# Module_Relay_UART_CAN.net
KiCad netlist of a schematic drawn in Altium Designer
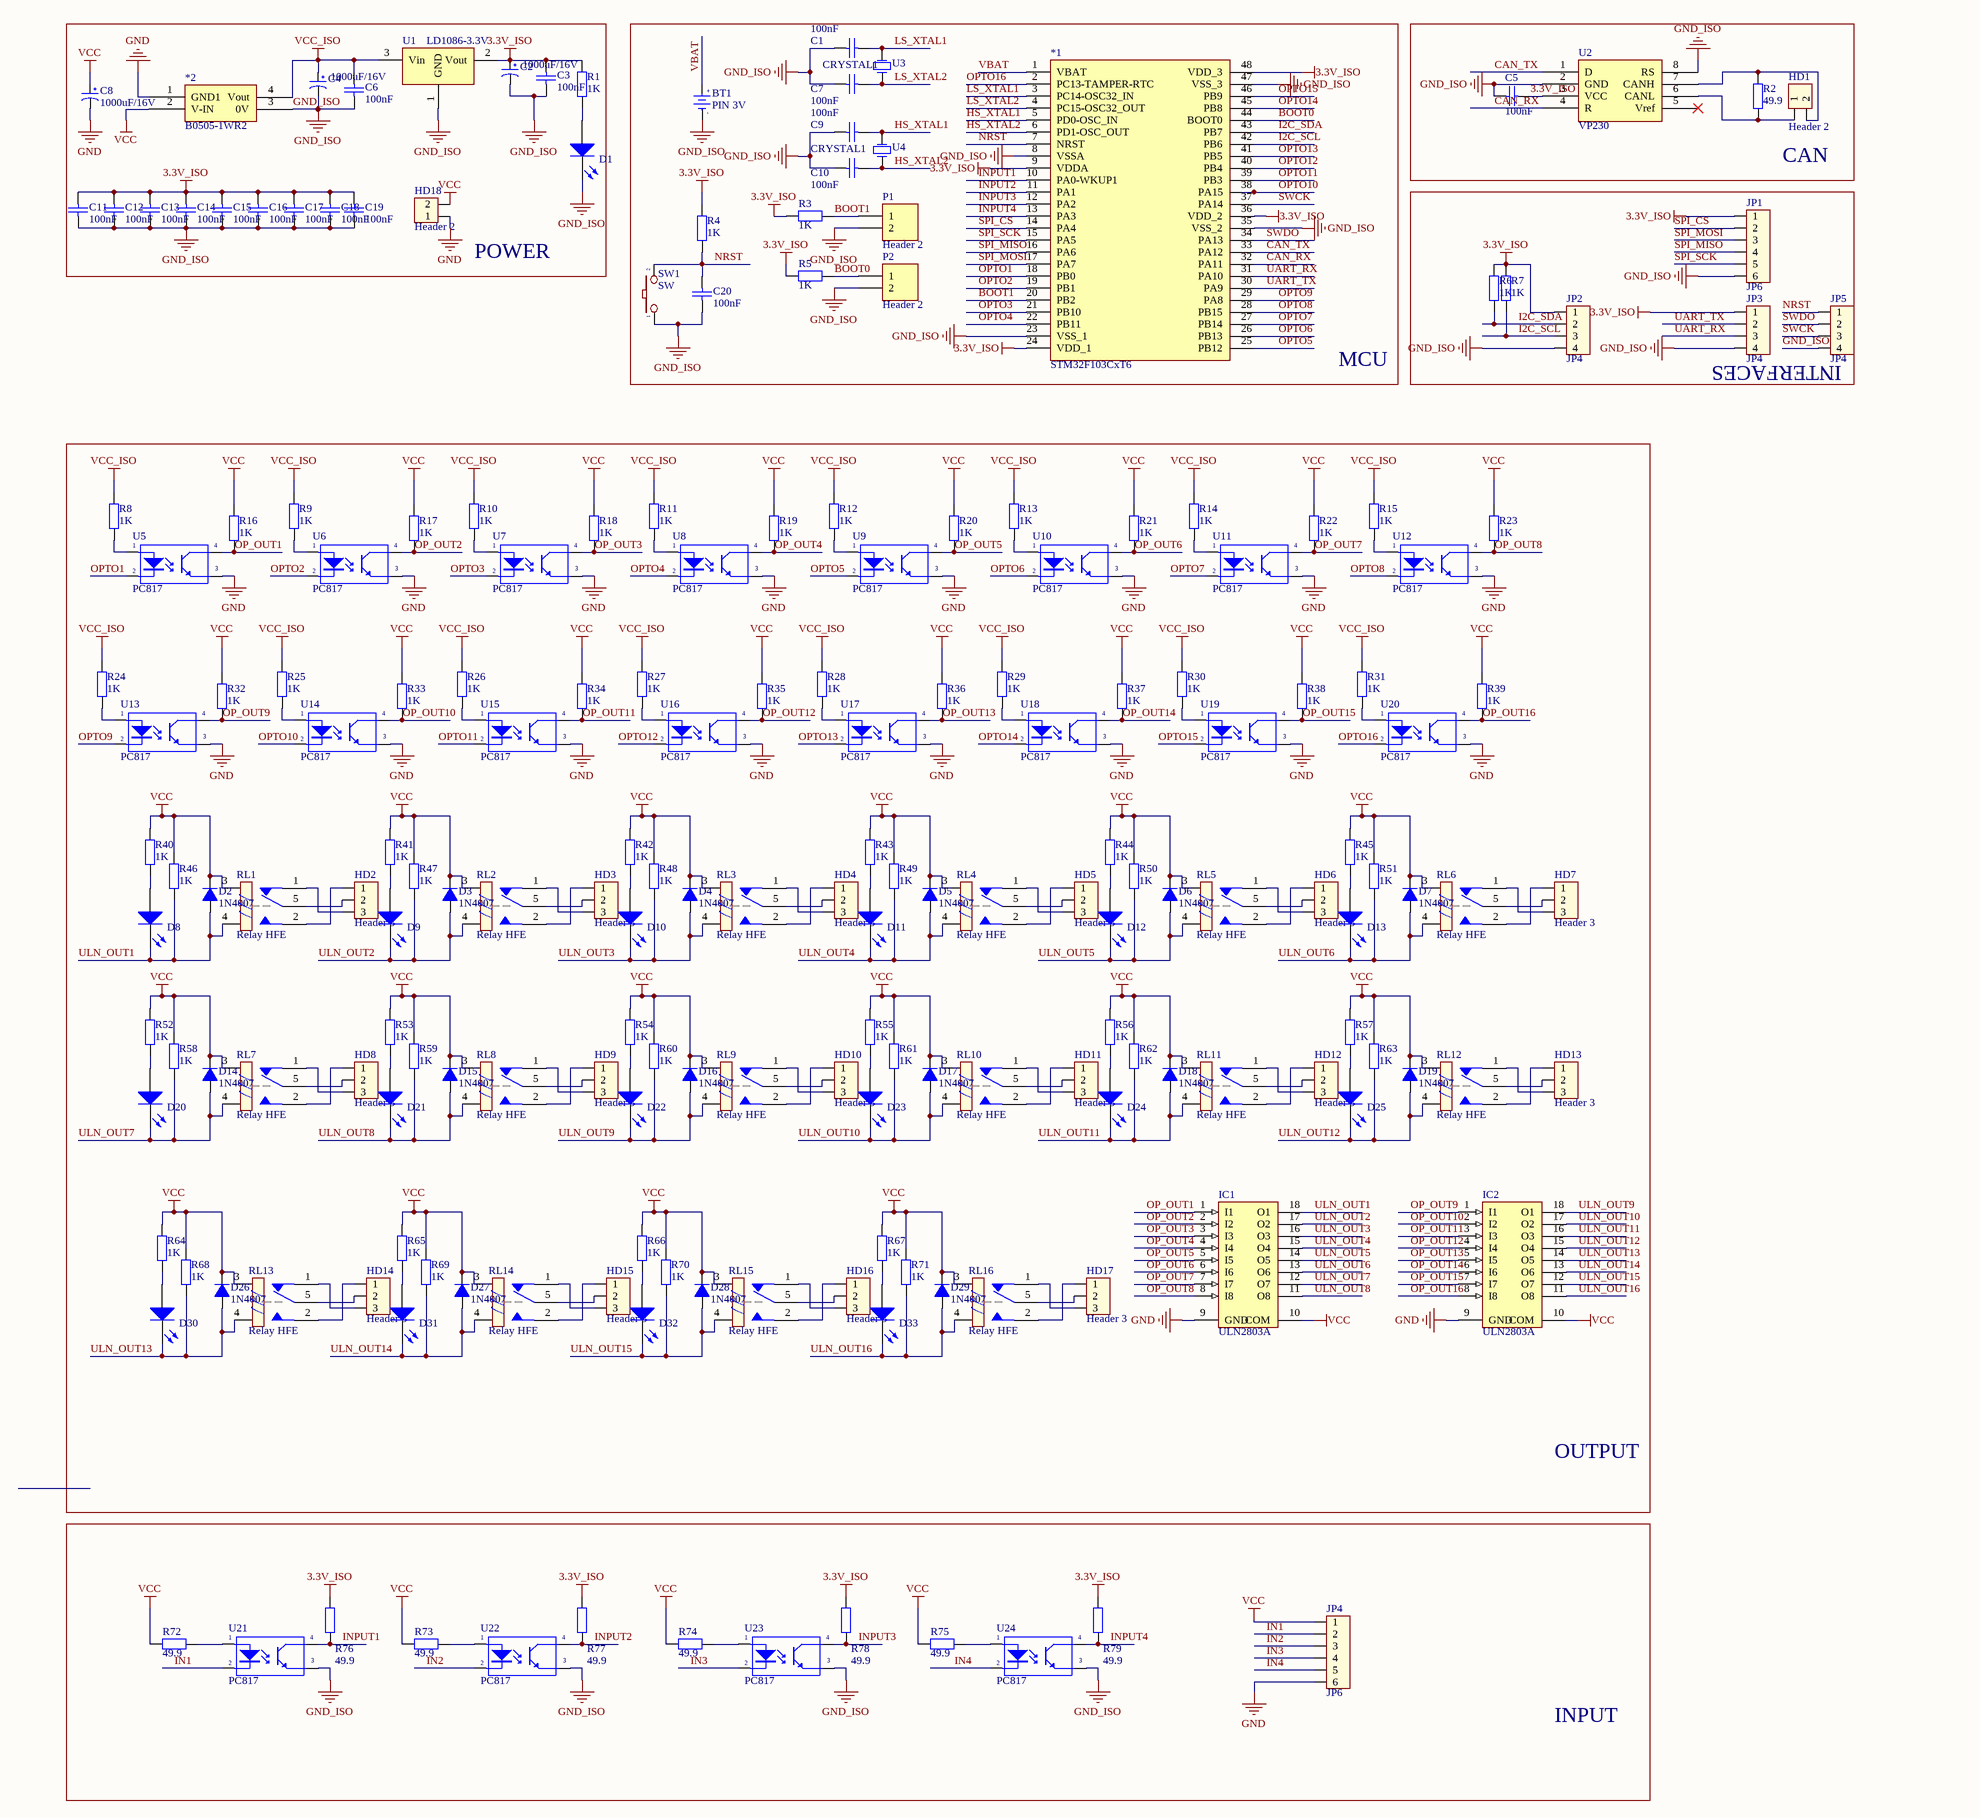
[diagram p0: Module_Relay_UART_CAN.SchDoc]

(export (version "E")
  (design (tool "Eeschema 10.0.6"))
  (components
    (comp (ref "*1")
      (value "STM32F103CxT6")
      (footprint "LQFP48_N")
      (libsource (lib "HTSAIGON") (part "STM32F103CxT6"))
    )
    (comp (ref "*2")
      (value "B0505-1WR2")
      (footprint "B0505-1WR2")
      (libsource (lib "HTSAIGON") (part "B0505-1WR2"))
    )
    (comp (ref "BT1")
      (value "PIN 3V")
      (footprint "CR1220")
      (description "Battery 3VDC")
      (libsource (lib "HTSAIGON") (part "PIN 3V"))
    )
    (comp (ref "C1")
      (value "CAP")
      (footprint "CAP0805")
      (fields (field (name "CAP") "100nF"))
      (libsource (lib "HTSAIGON") (part "CAP"))
    )
    (comp (ref "C2")
      (value "1000uF/16V")
      (footprint "CAP2917")
      (description "Cap 1000uF/16V - 220uF/50V")
      (libsource (lib "HTSAIGON") (part "CP4"))
    )
    (comp (ref "C3")
      (value "CAP")
      (footprint "CAP0805")
      (fields (field (name "CAP") "100nF"))
      (libsource (lib "HTSAIGON") (part "CAP"))
    )
    (comp (ref "C4")
      (value "1000uF/16V")
      (footprint "CAP2917")
      (description "Cap 1000uF/16V - 220uF/50V")
      (libsource (lib "HTSAIGON") (part "CP4"))
    )
    (comp (ref "C5")
      (value "CAP")
      (footprint "CAP0805")
      (fields (field (name "CAP") "100nF"))
      (libsource (lib "HTSAIGON") (part "CAP"))
    )
    (comp (ref "C6")
      (value "CAP")
      (footprint "CAP0805")
      (fields (field (name "CAP") "100nF"))
      (libsource (lib "HTSAIGON") (part "CAP"))
    )
    (comp (ref "C7")
      (value "CAP")
      (footprint "CAP0805")
      (fields (field (name "CAP") "100nF"))
      (libsource (lib "HTSAIGON") (part "CAP"))
    )
    (comp (ref "C8")
      (value "1000uF/16V")
      (footprint "CAP2917")
      (description "Cap 1000uF/16V - 220uF/50V")
      (libsource (lib "HTSAIGON") (part "CP4"))
    )
    (comp (ref "C9")
      (value "CAP")
      (footprint "CAP0805")
      (fields (field (name "CAP") "100nF"))
      (libsource (lib "HTSAIGON") (part "CAP"))
    )
    (comp (ref "C10")
      (value "CAP")
      (footprint "CAP0805")
      (fields (field (name "CAP") "100nF"))
      (libsource (lib "HTSAIGON") (part "CAP"))
    )
    (comp (ref "C11")
      (value "CAP")
      (footprint "CAP0805")
      (fields (field (name "CAP") "100nF"))
      (libsource (lib "HTSAIGON") (part "CAP"))
    )
    (comp (ref "C12")
      (value "CAP")
      (footprint "CAP0805")
      (fields (field (name "CAP") "100nF"))
      (libsource (lib "HTSAIGON") (part "CAP"))
    )
    (comp (ref "C13")
      (value "CAP")
      (footprint "CAP0805")
      (fields (field (name "CAP") "100nF"))
      (libsource (lib "HTSAIGON") (part "CAP"))
    )
    (comp (ref "C14")
      (value "CAP")
      (footprint "CAP0805")
      (fields (field (name "CAP") "100nF"))
      (libsource (lib "HTSAIGON") (part "CAP"))
    )
    (comp (ref "C15")
      (value "CAP")
      (footprint "CAP0805")
      (fields (field (name "CAP") "100nF"))
      (libsource (lib "HTSAIGON") (part "CAP"))
    )
    (comp (ref "C16")
      (value "CAP")
      (footprint "CAP0805")
      (fields (field (name "CAP") "100nF"))
      (libsource (lib "HTSAIGON") (part "CAP"))
    )
    (comp (ref "C17")
      (value "CAP")
      (footprint "CAP0805")
      (fields (field (name "CAP") "100nF"))
      (libsource (lib "HTSAIGON") (part "CAP"))
    )
    (comp (ref "C18")
      (value "CAP")
      (footprint "CAP0805")
      (fields (field (name "CAP") "100nF"))
      (libsource (lib "HTSAIGON") (part "CAP"))
    )
    (comp (ref "C19")
      (value "CAP")
      (footprint "CAP0805")
      (fields (field (name "CAP") "100nF"))
      (libsource (lib "HTSAIGON") (part "CAP"))
    )
    (comp (ref "C20")
      (value "CAP")
      (footprint "CAP0805")
      (fields (field (name "CAP") "100nF"))
      (libsource (lib "HTSAIGON") (part "CAP"))
    )
    (comp (ref "D1") (value "LED") (footprint "LED0805") (libsource (lib "HTSAIGON") (part "LED1")))
    (comp (ref "D2")
      (value "1N4007")
      (footprint "D1A")
      (description "Diode 1A")
      (libsource (lib "HTSAIGON") (part "D1A"))
    )
    (comp (ref "D3")
      (value "1N4007")
      (footprint "D1A")
      (description "Diode 1A")
      (libsource (lib "HTSAIGON") (part "D1A"))
    )
    (comp (ref "D4")
      (value "1N4007")
      (footprint "D1A")
      (description "Diode 1A")
      (libsource (lib "HTSAIGON") (part "D1A"))
    )
    (comp (ref "D5")
      (value "1N4007")
      (footprint "D1A")
      (description "Diode 1A")
      (libsource (lib "HTSAIGON") (part "D1A"))
    )
    (comp (ref "D6")
      (value "1N4007")
      (footprint "D1A")
      (description "Diode 1A")
      (libsource (lib "HTSAIGON") (part "D1A"))
    )
    (comp (ref "D7")
      (value "1N4007")
      (footprint "D1A")
      (description "Diode 1A")
      (libsource (lib "HTSAIGON") (part "D1A"))
    )
    (comp (ref "D8") (value "LED") (footprint "LED0805") (libsource (lib "HTSAIGON") (part "LED1")))
    (comp (ref "D9") (value "LED") (footprint "LED0805") (libsource (lib "HTSAIGON") (part "LED1")))
    (comp (ref "D10") (value "LED") (footprint "LED0805") (libsource (lib "HTSAIGON") (part "LED1")))
    (comp (ref "D11") (value "LED") (footprint "LED0805") (libsource (lib "HTSAIGON") (part "LED1")))
    (comp (ref "D12") (value "LED") (footprint "LED0805") (libsource (lib "HTSAIGON") (part "LED1")))
    (comp (ref "D13") (value "LED") (footprint "LED0805") (libsource (lib "HTSAIGON") (part "LED1")))
    (comp (ref "D14")
      (value "1N4007")
      (footprint "D1A")
      (description "Diode 1A")
      (libsource (lib "HTSAIGON") (part "D1A"))
    )
    (comp (ref "D15")
      (value "1N4007")
      (footprint "D1A")
      (description "Diode 1A")
      (libsource (lib "HTSAIGON") (part "D1A"))
    )
    (comp (ref "D16")
      (value "1N4007")
      (footprint "D1A")
      (description "Diode 1A")
      (libsource (lib "HTSAIGON") (part "D1A"))
    )
    (comp (ref "D17")
      (value "1N4007")
      (footprint "D1A")
      (description "Diode 1A")
      (libsource (lib "HTSAIGON") (part "D1A"))
    )
    (comp (ref "D18")
      (value "1N4007")
      (footprint "D1A")
      (description "Diode 1A")
      (libsource (lib "HTSAIGON") (part "D1A"))
    )
    (comp (ref "D19")
      (value "1N4007")
      (footprint "D1A")
      (description "Diode 1A")
      (libsource (lib "HTSAIGON") (part "D1A"))
    )
    (comp (ref "D20") (value "LED") (footprint "LED0805") (libsource (lib "HTSAIGON") (part "LED1")))
    (comp (ref "D21") (value "LED") (footprint "LED0805") (libsource (lib "HTSAIGON") (part "LED1")))
    (comp (ref "D22") (value "LED") (footprint "LED0805") (libsource (lib "HTSAIGON") (part "LED1")))
    (comp (ref "D23") (value "LED") (footprint "LED0805") (libsource (lib "HTSAIGON") (part "LED1")))
    (comp (ref "D24") (value "LED") (footprint "LED0805") (libsource (lib "HTSAIGON") (part "LED1")))
    (comp (ref "D25") (value "LED") (footprint "LED0805") (libsource (lib "HTSAIGON") (part "LED1")))
    (comp (ref "D26")
      (value "1N4007")
      (footprint "D1A")
      (description "Diode 1A")
      (libsource (lib "HTSAIGON") (part "D1A"))
    )
    (comp (ref "D27")
      (value "1N4007")
      (footprint "D1A")
      (description "Diode 1A")
      (libsource (lib "HTSAIGON") (part "D1A"))
    )
    (comp (ref "D28")
      (value "1N4007")
      (footprint "D1A")
      (description "Diode 1A")
      (libsource (lib "HTSAIGON") (part "D1A"))
    )
    (comp (ref "D29")
      (value "1N4007")
      (footprint "D1A")
      (description "Diode 1A")
      (libsource (lib "HTSAIGON") (part "D1A"))
    )
    (comp (ref "D30") (value "LED") (footprint "LED0805") (libsource (lib "HTSAIGON") (part "LED1")))
    (comp (ref "D31") (value "LED") (footprint "LED0805") (libsource (lib "HTSAIGON") (part "LED1")))
    (comp (ref "D32") (value "LED") (footprint "LED0805") (libsource (lib "HTSAIGON") (part "LED1")))
    (comp (ref "D33") (value "LED") (footprint "LED0805") (libsource (lib "HTSAIGON") (part "LED1")))
    (comp (ref "HD1")
      (value "Header 2")
      (footprint "HED2T")
      (description "Header 2 (Green)")
      (libsource (lib "") (part "Hed2_1"))
    )
    (comp (ref "HD2")
      (value "Header 3")
      (footprint "HED3T")
      (description "Header 3 (Green)")
      (libsource (lib "HTSAIGON") (part "Hed3"))
    )
    (comp (ref "HD3")
      (value "Header 3")
      (footprint "HED3T")
      (description "Header 3 (Green)")
      (libsource (lib "HTSAIGON") (part "Hed3"))
    )
    (comp (ref "HD4")
      (value "Header 3")
      (footprint "HED3T")
      (description "Header 3 (Green)")
      (libsource (lib "HTSAIGON") (part "Hed3"))
    )
    (comp (ref "HD5")
      (value "Header 3")
      (footprint "HED3T")
      (description "Header 3 (Green)")
      (libsource (lib "HTSAIGON") (part "Hed3"))
    )
    (comp (ref "HD6")
      (value "Header 3")
      (footprint "HED3T")
      (description "Header 3 (Green)")
      (libsource (lib "HTSAIGON") (part "Hed3"))
    )
    (comp (ref "HD7")
      (value "Header 3")
      (footprint "HED3T")
      (description "Header 3 (Green)")
      (libsource (lib "HTSAIGON") (part "Hed3"))
    )
    (comp (ref "HD8")
      (value "Header 3")
      (footprint "HED3T")
      (description "Header 3 (Green)")
      (libsource (lib "HTSAIGON") (part "Hed3"))
    )
    (comp (ref "HD9")
      (value "Header 3")
      (footprint "HED3T")
      (description "Header 3 (Green)")
      (libsource (lib "HTSAIGON") (part "Hed3"))
    )
    (comp (ref "HD10")
      (value "Header 3")
      (footprint "HED3T")
      (description "Header 3 (Green)")
      (libsource (lib "HTSAIGON") (part "Hed3"))
    )
    (comp (ref "HD11")
      (value "Header 3")
      (footprint "HED3T")
      (description "Header 3 (Green)")
      (libsource (lib "HTSAIGON") (part "Hed3"))
    )
    (comp (ref "HD12")
      (value "Header 3")
      (footprint "HED3T")
      (description "Header 3 (Green)")
      (libsource (lib "HTSAIGON") (part "Hed3"))
    )
    (comp (ref "HD13")
      (value "Header 3")
      (footprint "HED3T")
      (description "Header 3 (Green)")
      (libsource (lib "HTSAIGON") (part "Hed3"))
    )
    (comp (ref "HD14")
      (value "Header 3")
      (footprint "HED3T")
      (description "Header 3 (Green)")
      (libsource (lib "HTSAIGON") (part "Hed3"))
    )
    (comp (ref "HD15")
      (value "Header 3")
      (footprint "HED3T")
      (description "Header 3 (Green)")
      (libsource (lib "HTSAIGON") (part "Hed3"))
    )
    (comp (ref "HD16")
      (value "Header 3")
      (footprint "HED3T")
      (description "Header 3 (Green)")
      (libsource (lib "HTSAIGON") (part "Hed3"))
    )
    (comp (ref "HD17")
      (value "Header 3")
      (footprint "HED3T")
      (description "Header 3 (Green)")
      (libsource (lib "HTSAIGON") (part "Hed3"))
    )
    (comp (ref "HD18")
      (value "Header 2")
      (footprint "HED2T")
      (description "Header 2 (Green)")
      (libsource (lib "HTSAIGON") (part "Hed2"))
    )
    (comp (ref "IC1")
      (value "ULN2803A")
      (footprint "SOP18")
      (description "High-Voltage, High-Current Darlington Array")
      (fields (field (name "PUBLISHER") "Altium Limited"))
      (libsource (lib "HTSAIGON") (part "ULN2803A"))
    )
    (comp (ref "IC2")
      (value "ULN2803A")
      (footprint "SOP18")
      (description "High-Voltage, High-Current Darlington Array")
      (fields (field (name "PUBLISHER") "Altium Limited"))
      (libsource (lib "HTSAIGON") (part "ULN2803A"))
    )
    (comp (ref "JP1")
      (value "JP6")
      (footprint "CON6")
      (description "Connector 6")
      (libsource (lib "HTSAIGON") (part "Con6"))
    )
    (comp (ref "JP2")
      (value "JP4")
      (footprint "CON4")
      (description "Connector 4")
      (libsource (lib "HTSAIGON") (part "Con4"))
    )
    (comp (ref "JP3")
      (value "JP4")
      (footprint "CON4")
      (description "Connector 4")
      (libsource (lib "HTSAIGON") (part "Con4"))
    )
    (comp (ref "JP4")
      (value "JP6")
      (footprint "CON6")
      (description "Connector 6")
      (libsource (lib "HTSAIGON") (part "Con6"))
    )
    (comp (ref "JP5")
      (value "JP4")
      (footprint "CON4")
      (description "Connector 4")
      (libsource (lib "HTSAIGON") (part "Con4"))
    )
    (comp (ref "P1")
      (value "Header 2")
      (footprint "HDR1X2")
      (description "Header, 2-Pin")
      (fields (field (name "PUBLISHER") "Altium Limited"))
      (libsource (lib "Miscellaneous Connectors") (part "Header 2"))
    )
    (comp (ref "P2")
      (value "Header 2")
      (footprint "HDR1X2")
      (description "Header, 2-Pin")
      (fields (field (name "PUBLISHER") "Altium Limited"))
      (libsource (lib "Miscellaneous Connectors") (part "Header 2"))
    )
    (comp (ref "R1")
      (value "RES")
      (footprint "0805")
      (fields (field (name "RES") "1K"))
      (libsource (lib "HTSAIGON") (part "RES"))
    )
    (comp (ref "R2")
      (value "RES")
      (footprint "0805")
      (fields (field (name "RES") "49.9"))
      (libsource (lib "") (part "RES_1"))
    )
    (comp (ref "R3")
      (value "RES")
      (footprint "0805")
      (fields (field (name "RES") "1K"))
      (libsource (lib "") (part "RES_3"))
    )
    (comp (ref "R4")
      (value "RES")
      (footprint "0805")
      (fields (field (name "RES") "1K"))
      (libsource (lib "HTSAIGON") (part "RES"))
    )
    (comp (ref "R5")
      (value "RES")
      (footprint "0805")
      (fields (field (name "RES") "1K"))
      (libsource (lib "") (part "RES_3"))
    )
    (comp (ref "R6")
      (value "RES")
      (footprint "0805")
      (fields (field (name "RES") "1K"))
      (libsource (lib "HTSAIGON") (part "RES"))
    )
    (comp (ref "R7")
      (value "RES")
      (footprint "0805")
      (fields (field (name "RES") "1K"))
      (libsource (lib "HTSAIGON") (part "RES"))
    )
    (comp (ref "R8")
      (value "RES")
      (footprint "0805")
      (fields (field (name "RES") "1K"))
      (libsource (lib "") (part "RES_1"))
    )
    (comp (ref "R9")
      (value "RES")
      (footprint "0805")
      (fields (field (name "RES") "1K"))
      (libsource (lib "") (part "RES_1"))
    )
    (comp (ref "R10")
      (value "RES")
      (footprint "0805")
      (fields (field (name "RES") "1K"))
      (libsource (lib "") (part "RES_1"))
    )
    (comp (ref "R11")
      (value "RES")
      (footprint "0805")
      (fields (field (name "RES") "1K"))
      (libsource (lib "") (part "RES_1"))
    )
    (comp (ref "R12")
      (value "RES")
      (footprint "0805")
      (fields (field (name "RES") "1K"))
      (libsource (lib "") (part "RES_1"))
    )
    (comp (ref "R13")
      (value "RES")
      (footprint "0805")
      (fields (field (name "RES") "1K"))
      (libsource (lib "") (part "RES_1"))
    )
    (comp (ref "R14")
      (value "RES")
      (footprint "0805")
      (fields (field (name "RES") "1K"))
      (libsource (lib "") (part "RES_1"))
    )
    (comp (ref "R15")
      (value "RES")
      (footprint "0805")
      (fields (field (name "RES") "1K"))
      (libsource (lib "") (part "RES_1"))
    )
    (comp (ref "R16")
      (value "RES")
      (footprint "0805")
      (fields (field (name "RES") "1K"))
      (libsource (lib "HTSAIGON") (part "RES"))
    )
    (comp (ref "R17")
      (value "RES")
      (footprint "0805")
      (fields (field (name "RES") "1K"))
      (libsource (lib "HTSAIGON") (part "RES"))
    )
    (comp (ref "R18")
      (value "RES")
      (footprint "0805")
      (fields (field (name "RES") "1K"))
      (libsource (lib "HTSAIGON") (part "RES"))
    )
    (comp (ref "R19")
      (value "RES")
      (footprint "0805")
      (fields (field (name "RES") "1K"))
      (libsource (lib "HTSAIGON") (part "RES"))
    )
    (comp (ref "R20")
      (value "RES")
      (footprint "0805")
      (fields (field (name "RES") "1K"))
      (libsource (lib "HTSAIGON") (part "RES"))
    )
    (comp (ref "R21")
      (value "RES")
      (footprint "0805")
      (fields (field (name "RES") "1K"))
      (libsource (lib "HTSAIGON") (part "RES"))
    )
    (comp (ref "R22")
      (value "RES")
      (footprint "0805")
      (fields (field (name "RES") "1K"))
      (libsource (lib "HTSAIGON") (part "RES"))
    )
    (comp (ref "R23")
      (value "RES")
      (footprint "0805")
      (fields (field (name "RES") "1K"))
      (libsource (lib "HTSAIGON") (part "RES"))
    )
    (comp (ref "R24")
      (value "RES")
      (footprint "0805")
      (fields (field (name "RES") "1K"))
      (libsource (lib "") (part "RES_1"))
    )
    (comp (ref "R25")
      (value "RES")
      (footprint "0805")
      (fields (field (name "RES") "1K"))
      (libsource (lib "") (part "RES_1"))
    )
    (comp (ref "R26")
      (value "RES")
      (footprint "0805")
      (fields (field (name "RES") "1K"))
      (libsource (lib "") (part "RES_1"))
    )
    (comp (ref "R27")
      (value "RES")
      (footprint "0805")
      (fields (field (name "RES") "1K"))
      (libsource (lib "") (part "RES_1"))
    )
    (comp (ref "R28")
      (value "RES")
      (footprint "0805")
      (fields (field (name "RES") "1K"))
      (libsource (lib "") (part "RES_1"))
    )
    (comp (ref "R29")
      (value "RES")
      (footprint "0805")
      (fields (field (name "RES") "1K"))
      (libsource (lib "") (part "RES_1"))
    )
    (comp (ref "R30")
      (value "RES")
      (footprint "0805")
      (fields (field (name "RES") "1K"))
      (libsource (lib "") (part "RES_1"))
    )
    (comp (ref "R31")
      (value "RES")
      (footprint "0805")
      (fields (field (name "RES") "1K"))
      (libsource (lib "") (part "RES_1"))
    )
    (comp (ref "R32")
      (value "RES")
      (footprint "0805")
      (fields (field (name "RES") "1K"))
      (libsource (lib "HTSAIGON") (part "RES"))
    )
    (comp (ref "R33")
      (value "RES")
      (footprint "0805")
      (fields (field (name "RES") "1K"))
      (libsource (lib "HTSAIGON") (part "RES"))
    )
    (comp (ref "R34")
      (value "RES")
      (footprint "0805")
      (fields (field (name "RES") "1K"))
      (libsource (lib "HTSAIGON") (part "RES"))
    )
    (comp (ref "R35")
      (value "RES")
      (footprint "0805")
      (fields (field (name "RES") "1K"))
      (libsource (lib "HTSAIGON") (part "RES"))
    )
    (comp (ref "R36")
      (value "RES")
      (footprint "0805")
      (fields (field (name "RES") "1K"))
      (libsource (lib "HTSAIGON") (part "RES"))
    )
    (comp (ref "R37")
      (value "RES")
      (footprint "0805")
      (fields (field (name "RES") "1K"))
      (libsource (lib "HTSAIGON") (part "RES"))
    )
    (comp (ref "R38")
      (value "RES")
      (footprint "0805")
      (fields (field (name "RES") "1K"))
      (libsource (lib "HTSAIGON") (part "RES"))
    )
    (comp (ref "R39")
      (value "RES")
      (footprint "0805")
      (fields (field (name "RES") "1K"))
      (libsource (lib "HTSAIGON") (part "RES"))
    )
    (comp (ref "R40")
      (value "RES")
      (footprint "0805")
      (fields (field (name "RES") "1K"))
      (libsource (lib "HTSAIGON") (part "RES"))
    )
    (comp (ref "R41")
      (value "RES")
      (footprint "0805")
      (fields (field (name "RES") "1K"))
      (libsource (lib "HTSAIGON") (part "RES"))
    )
    (comp (ref "R42")
      (value "RES")
      (footprint "0805")
      (fields (field (name "RES") "1K"))
      (libsource (lib "HTSAIGON") (part "RES"))
    )
    (comp (ref "R43")
      (value "RES")
      (footprint "0805")
      (fields (field (name "RES") "1K"))
      (libsource (lib "HTSAIGON") (part "RES"))
    )
    (comp (ref "R44")
      (value "RES")
      (footprint "0805")
      (fields (field (name "RES") "1K"))
      (libsource (lib "HTSAIGON") (part "RES"))
    )
    (comp (ref "R45")
      (value "RES")
      (footprint "0805")
      (fields (field (name "RES") "1K"))
      (libsource (lib "HTSAIGON") (part "RES"))
    )
    (comp (ref "R46")
      (value "RES")
      (footprint "0805")
      (fields (field (name "RES") "1K"))
      (libsource (lib "HTSAIGON") (part "RES"))
    )
    (comp (ref "R47")
      (value "RES")
      (footprint "0805")
      (fields (field (name "RES") "1K"))
      (libsource (lib "HTSAIGON") (part "RES"))
    )
    (comp (ref "R48")
      (value "RES")
      (footprint "0805")
      (fields (field (name "RES") "1K"))
      (libsource (lib "HTSAIGON") (part "RES"))
    )
    (comp (ref "R49")
      (value "RES")
      (footprint "0805")
      (fields (field (name "RES") "1K"))
      (libsource (lib "HTSAIGON") (part "RES"))
    )
    (comp (ref "R50")
      (value "RES")
      (footprint "0805")
      (fields (field (name "RES") "1K"))
      (libsource (lib "HTSAIGON") (part "RES"))
    )
    (comp (ref "R51")
      (value "RES")
      (footprint "0805")
      (fields (field (name "RES") "1K"))
      (libsource (lib "HTSAIGON") (part "RES"))
    )
    (comp (ref "R52")
      (value "RES")
      (footprint "0805")
      (fields (field (name "RES") "1K"))
      (libsource (lib "HTSAIGON") (part "RES"))
    )
    (comp (ref "R53")
      (value "RES")
      (footprint "0805")
      (fields (field (name "RES") "1K"))
      (libsource (lib "HTSAIGON") (part "RES"))
    )
    (comp (ref "R54")
      (value "RES")
      (footprint "0805")
      (fields (field (name "RES") "1K"))
      (libsource (lib "HTSAIGON") (part "RES"))
    )
    (comp (ref "R55")
      (value "RES")
      (footprint "0805")
      (fields (field (name "RES") "1K"))
      (libsource (lib "HTSAIGON") (part "RES"))
    )
    (comp (ref "R56")
      (value "RES")
      (footprint "0805")
      (fields (field (name "RES") "1K"))
      (libsource (lib "HTSAIGON") (part "RES"))
    )
    (comp (ref "R57")
      (value "RES")
      (footprint "0805")
      (fields (field (name "RES") "1K"))
      (libsource (lib "HTSAIGON") (part "RES"))
    )
    (comp (ref "R58")
      (value "RES")
      (footprint "0805")
      (fields (field (name "RES") "1K"))
      (libsource (lib "HTSAIGON") (part "RES"))
    )
    (comp (ref "R59")
      (value "RES")
      (footprint "0805")
      (fields (field (name "RES") "1K"))
      (libsource (lib "HTSAIGON") (part "RES"))
    )
    (comp (ref "R60")
      (value "RES")
      (footprint "0805")
      (fields (field (name "RES") "1K"))
      (libsource (lib "HTSAIGON") (part "RES"))
    )
    (comp (ref "R61")
      (value "RES")
      (footprint "0805")
      (fields (field (name "RES") "1K"))
      (libsource (lib "HTSAIGON") (part "RES"))
    )
    (comp (ref "R62")
      (value "RES")
      (footprint "0805")
      (fields (field (name "RES") "1K"))
      (libsource (lib "HTSAIGON") (part "RES"))
    )
    (comp (ref "R63")
      (value "RES")
      (footprint "0805")
      (fields (field (name "RES") "1K"))
      (libsource (lib "HTSAIGON") (part "RES"))
    )
    (comp (ref "R64")
      (value "RES")
      (footprint "0805")
      (fields (field (name "RES") "1K"))
      (libsource (lib "HTSAIGON") (part "RES"))
    )
    (comp (ref "R65")
      (value "RES")
      (footprint "0805")
      (fields (field (name "RES") "1K"))
      (libsource (lib "HTSAIGON") (part "RES"))
    )
    (comp (ref "R66")
      (value "RES")
      (footprint "0805")
      (fields (field (name "RES") "1K"))
      (libsource (lib "HTSAIGON") (part "RES"))
    )
    (comp (ref "R67")
      (value "RES")
      (footprint "0805")
      (fields (field (name "RES") "1K"))
      (libsource (lib "HTSAIGON") (part "RES"))
    )
    (comp (ref "R68")
      (value "RES")
      (footprint "0805")
      (fields (field (name "RES") "1K"))
      (libsource (lib "HTSAIGON") (part "RES"))
    )
    (comp (ref "R69")
      (value "RES")
      (footprint "0805")
      (fields (field (name "RES") "1K"))
      (libsource (lib "HTSAIGON") (part "RES"))
    )
    (comp (ref "R70")
      (value "RES")
      (footprint "0805")
      (fields (field (name "RES") "1K"))
      (libsource (lib "HTSAIGON") (part "RES"))
    )
    (comp (ref "R71")
      (value "RES")
      (footprint "0805")
      (fields (field (name "RES") "1K"))
      (libsource (lib "HTSAIGON") (part "RES"))
    )
    (comp (ref "R72")
      (value "RES")
      (footprint "0805")
      (fields (field (name "RES") "49.9"))
      (libsource (lib "") (part "RES_2"))
    )
    (comp (ref "R73")
      (value "RES")
      (footprint "0805")
      (fields (field (name "RES") "49.9"))
      (libsource (lib "") (part "RES_2"))
    )
    (comp (ref "R74")
      (value "RES")
      (footprint "0805")
      (fields (field (name "RES") "49.9"))
      (libsource (lib "") (part "RES_2"))
    )
    (comp (ref "R75")
      (value "RES")
      (footprint "0805")
      (fields (field (name "RES") "49.9"))
      (libsource (lib "") (part "RES_2"))
    )
    (comp (ref "R76")
      (value "RES")
      (footprint "0805")
      (fields (field (name "RES") "49.9"))
      (libsource (lib "HTSAIGON") (part "RES"))
    )
    (comp (ref "R77")
      (value "RES")
      (footprint "0805")
      (fields (field (name "RES") "49.9"))
      (libsource (lib "HTSAIGON") (part "RES"))
    )
    (comp (ref "R78")
      (value "RES")
      (footprint "0805")
      (fields (field (name "RES") "49.9"))
      (libsource (lib "HTSAIGON") (part "RES"))
    )
    (comp (ref "R79")
      (value "RES")
      (footprint "0805")
      (fields (field (name "RES") "49.9"))
      (libsource (lib "HTSAIGON") (part "RES"))
    )
    (comp (ref "RL1")
      (value "Relay HFE")
      (footprint "RELAY HFE")
      (description "Relay SPDT,10A - 12VDC 5 Pin")
      (libsource (lib "HTSAIGON") (part "Relay HFE"))
    )
    (comp (ref "RL2")
      (value "Relay HFE")
      (footprint "RELAY HFE")
      (description "Relay SPDT,10A - 12VDC 5 Pin")
      (libsource (lib "HTSAIGON") (part "Relay HFE"))
    )
    (comp (ref "RL3")
      (value "Relay HFE")
      (footprint "RELAY HFE")
      (description "Relay SPDT,10A - 12VDC 5 Pin")
      (libsource (lib "HTSAIGON") (part "Relay HFE"))
    )
    (comp (ref "RL4")
      (value "Relay HFE")
      (footprint "RELAY HFE")
      (description "Relay SPDT,10A - 12VDC 5 Pin")
      (libsource (lib "HTSAIGON") (part "Relay HFE"))
    )
    (comp (ref "RL5")
      (value "Relay HFE")
      (footprint "RELAY HFE")
      (description "Relay SPDT,10A - 12VDC 5 Pin")
      (libsource (lib "HTSAIGON") (part "Relay HFE"))
    )
    (comp (ref "RL6")
      (value "Relay HFE")
      (footprint "RELAY HFE")
      (description "Relay SPDT,10A - 12VDC 5 Pin")
      (libsource (lib "HTSAIGON") (part "Relay HFE"))
    )
    (comp (ref "RL7")
      (value "Relay HFE")
      (footprint "RELAY HFE")
      (description "Relay SPDT,10A - 12VDC 5 Pin")
      (libsource (lib "HTSAIGON") (part "Relay HFE"))
    )
    (comp (ref "RL8")
      (value "Relay HFE")
      (footprint "RELAY HFE")
      (description "Relay SPDT,10A - 12VDC 5 Pin")
      (libsource (lib "HTSAIGON") (part "Relay HFE"))
    )
    (comp (ref "RL9")
      (value "Relay HFE")
      (footprint "RELAY HFE")
      (description "Relay SPDT,10A - 12VDC 5 Pin")
      (libsource (lib "HTSAIGON") (part "Relay HFE"))
    )
    (comp (ref "RL10")
      (value "Relay HFE")
      (footprint "RELAY HFE")
      (description "Relay SPDT,10A - 12VDC 5 Pin")
      (libsource (lib "HTSAIGON") (part "Relay HFE"))
    )
    (comp (ref "RL11")
      (value "Relay HFE")
      (footprint "RELAY HFE")
      (description "Relay SPDT,10A - 12VDC 5 Pin")
      (libsource (lib "HTSAIGON") (part "Relay HFE"))
    )
    (comp (ref "RL12")
      (value "Relay HFE")
      (footprint "RELAY HFE")
      (description "Relay SPDT,10A - 12VDC 5 Pin")
      (libsource (lib "HTSAIGON") (part "Relay HFE"))
    )
    (comp (ref "RL13")
      (value "Relay HFE")
      (footprint "RELAY HFE")
      (description "Relay SPDT,10A - 12VDC 5 Pin")
      (libsource (lib "HTSAIGON") (part "Relay HFE"))
    )
    (comp (ref "RL14")
      (value "Relay HFE")
      (footprint "RELAY HFE")
      (description "Relay SPDT,10A - 12VDC 5 Pin")
      (libsource (lib "HTSAIGON") (part "Relay HFE"))
    )
    (comp (ref "RL15")
      (value "Relay HFE")
      (footprint "RELAY HFE")
      (description "Relay SPDT,10A - 12VDC 5 Pin")
      (libsource (lib "HTSAIGON") (part "Relay HFE"))
    )
    (comp (ref "RL16")
      (value "Relay HFE")
      (footprint "RELAY HFE")
      (description "Relay SPDT,10A - 12VDC 5 Pin")
      (libsource (lib "HTSAIGON") (part "Relay HFE"))
    )
    (comp (ref "SW1")
      (value "SW")
      (footprint "SW2PIN-HT")
      (description "Switch button 2 pin")
      (libsource (lib "HTSAIGON") (part "SW2"))
    )
    (comp (ref "U1")
      (value "LD1086-3.3V")
      (footprint "SOT223_L")
      (libsource (lib "HTSAIGON") (part "AP1117_3V3"))
    )
    (comp (ref "U2") (value "VP230") (footprint "SO-8") (libsource (lib "HTSAIGON") (part "SN65HVD230")))
    (comp (ref "U3") (value "CRYSTAL1") (footprint "0805") (libsource (lib "HTSAIGON") (part "CRYSTAL1")))
    (comp (ref "U4") (value "CRYSTAL1") (footprint "CRYSTAL2") (libsource (lib "HTSAIGON") (part "CRYSTAL1")))
    (comp (ref "U5")
      (value "PC817")
      (footprint "DIP4/W0.3")
      (description "Single Opto")
      (libsource (lib "HTSAIGON") (part "PC817"))
    )
    (comp (ref "U6")
      (value "PC817")
      (footprint "DIP4/W0.3")
      (description "Single Opto")
      (libsource (lib "HTSAIGON") (part "PC817"))
    )
    (comp (ref "U7")
      (value "PC817")
      (footprint "DIP4/W0.3")
      (description "Single Opto")
      (libsource (lib "HTSAIGON") (part "PC817"))
    )
    (comp (ref "U8")
      (value "PC817")
      (footprint "DIP4/W0.3")
      (description "Single Opto")
      (libsource (lib "HTSAIGON") (part "PC817"))
    )
    (comp (ref "U9")
      (value "PC817")
      (footprint "DIP4/W0.3")
      (description "Single Opto")
      (libsource (lib "HTSAIGON") (part "PC817"))
    )
    (comp (ref "U10")
      (value "PC817")
      (footprint "DIP4/W0.3")
      (description "Single Opto")
      (libsource (lib "HTSAIGON") (part "PC817"))
    )
    (comp (ref "U11")
      (value "PC817")
      (footprint "DIP4/W0.3")
      (description "Single Opto")
      (libsource (lib "HTSAIGON") (part "PC817"))
    )
    (comp (ref "U12")
      (value "PC817")
      (footprint "DIP4/W0.3")
      (description "Single Opto")
      (libsource (lib "HTSAIGON") (part "PC817"))
    )
    (comp (ref "U13")
      (value "PC817")
      (footprint "DIP4/W0.3")
      (description "Single Opto")
      (libsource (lib "HTSAIGON") (part "PC817"))
    )
    (comp (ref "U14")
      (value "PC817")
      (footprint "DIP4/W0.3")
      (description "Single Opto")
      (libsource (lib "HTSAIGON") (part "PC817"))
    )
    (comp (ref "U15")
      (value "PC817")
      (footprint "DIP4/W0.3")
      (description "Single Opto")
      (libsource (lib "HTSAIGON") (part "PC817"))
    )
    (comp (ref "U16")
      (value "PC817")
      (footprint "DIP4/W0.3")
      (description "Single Opto")
      (libsource (lib "HTSAIGON") (part "PC817"))
    )
    (comp (ref "U17")
      (value "PC817")
      (footprint "DIP4/W0.3")
      (description "Single Opto")
      (libsource (lib "HTSAIGON") (part "PC817"))
    )
    (comp (ref "U18")
      (value "PC817")
      (footprint "DIP4/W0.3")
      (description "Single Opto")
      (libsource (lib "HTSAIGON") (part "PC817"))
    )
    (comp (ref "U19")
      (value "PC817")
      (footprint "DIP4/W0.3")
      (description "Single Opto")
      (libsource (lib "HTSAIGON") (part "PC817"))
    )
    (comp (ref "U20")
      (value "PC817")
      (footprint "DIP4/W0.3")
      (description "Single Opto")
      (libsource (lib "HTSAIGON") (part "PC817"))
    )
    (comp (ref "U21")
      (value "PC817")
      (footprint "DIP4/W0.3")
      (description "Single Opto")
      (libsource (lib "HTSAIGON") (part "PC817"))
    )
    (comp (ref "U22")
      (value "PC817")
      (footprint "DIP4/W0.3")
      (description "Single Opto")
      (libsource (lib "HTSAIGON") (part "PC817"))
    )
    (comp (ref "U23")
      (value "PC817")
      (footprint "DIP4/W0.3")
      (description "Single Opto")
      (libsource (lib "HTSAIGON") (part "PC817"))
    )
    (comp (ref "U24")
      (value "PC817")
      (footprint "DIP4/W0.3")
      (description "Single Opto")
      (libsource (lib "HTSAIGON") (part "PC817"))
    )
  )
  (nets
    (net (code "1") (name "/BOOT0") (class "Default")
      (node (ref "*1") (pin "44") (pinfunction "BOOT0_44") (pintype "passive"))
      (node (ref "P2") (pin "1") (pinfunction "1_1") (pintype "passive"))
      (node (ref "R5") (pin "1") (pinfunction "1_1") (pintype "passive"))
    )
    (net (code "2") (name "/BOOT1") (class "Default")
      (node (ref "*1") (pin "20") (pinfunction "PB2_20") (pintype "passive"))
      (node (ref "P1") (pin "1") (pinfunction "1_1") (pintype "passive"))
      (node (ref "R3") (pin "1") (pinfunction "1_1") (pintype "passive"))
    )
    (net (code "3") (name "/CAN_RX") (class "Default")
      (node (ref "*1") (pin "32") (pinfunction "PA11_32") (pintype "passive"))
      (node (ref "U2") (pin "4") (pinfunction "R_4") (pintype "passive"))
    )
    (net (code "4") (name "/CAN_TX") (class "Default")
      (node (ref "*1") (pin "33") (pinfunction "PA12_33") (pintype "passive"))
      (node (ref "U2") (pin "1") (pinfunction "D_1") (pintype "passive"))
    )
    (net (code "5") (name "/HS_XTAL1") (class "Default")
      (node (ref "*1") (pin "5") (pinfunction "PD0-OSC_IN_5") (pintype "passive"))
      (node (ref "C9") (pin "1") (pinfunction "1_1") (pintype "passive"))
      (node (ref "U4") (pin "2") (pinfunction "OSC2_2") (pintype "passive"))
    )
    (net (code "6") (name "/HS_XTAL2") (class "Default")
      (node (ref "*1") (pin "6") (pinfunction "PD1-OSC_OUT_6") (pintype "passive"))
      (node (ref "C10") (pin "1") (pinfunction "1_1") (pintype "passive"))
      (node (ref "U4") (pin "1") (pinfunction "OSC1_1") (pintype "passive"))
    )
    (net (code "7") (name "/I2C_SCL") (class "Default")
      (node (ref "*1") (pin "42") (pinfunction "PB6_42") (pintype "passive"))
      (node (ref "JP2") (pin "3") (pinfunction "3_3") (pintype "passive"))
      (node (ref "R7") (pin "1") (pinfunction "1_1") (pintype "passive"))
    )
    (net (code "8") (name "/I2C_SDA") (class "Default")
      (node (ref "*1") (pin "43") (pinfunction "PB7_43") (pintype "passive"))
      (node (ref "JP2") (pin "2") (pinfunction "2_2") (pintype "passive"))
      (node (ref "R6") (pin "1") (pinfunction "1_1") (pintype "passive"))
    )
    (net (code "9") (name "/IN1") (class "Default")
      (node (ref "JP4") (pin "2") (pinfunction "2_2") (pintype "passive"))
      (node (ref "U21") (pin "2") (pinfunction "K_2") (pintype "passive"))
    )
    (net (code "10") (name "/IN2") (class "Default")
      (node (ref "JP4") (pin "3") (pinfunction "3_3") (pintype "passive"))
      (node (ref "U22") (pin "2") (pinfunction "K_2") (pintype "passive"))
    )
    (net (code "11") (name "/IN3") (class "Default")
      (node (ref "JP4") (pin "4") (pinfunction "4_4") (pintype "passive"))
      (node (ref "U23") (pin "2") (pinfunction "K_2") (pintype "passive"))
    )
    (net (code "12") (name "/IN4") (class "Default")
      (node (ref "JP4") (pin "5") (pinfunction "5_5") (pintype "passive"))
      (node (ref "U24") (pin "2") (pinfunction "K_2") (pintype "passive"))
    )
    (net (code "13") (name "/INPUT1") (class "Default")
      (node (ref "*1") (pin "10") (pinfunction "PA0-WKUP1_10") (pintype "passive"))
      (node (ref "R76") (pin "1") (pinfunction "1_1") (pintype "passive"))
      (node (ref "U21") (pin "4") (pinfunction "C_4") (pintype "passive"))
    )
    (net (code "14") (name "/INPUT2") (class "Default")
      (node (ref "*1") (pin "11") (pinfunction "PA1_11") (pintype "passive"))
      (node (ref "R77") (pin "1") (pinfunction "1_1") (pintype "passive"))
      (node (ref "U22") (pin "4") (pinfunction "C_4") (pintype "passive"))
    )
    (net (code "15") (name "/INPUT3") (class "Default")
      (node (ref "*1") (pin "12") (pinfunction "PA2_12") (pintype "passive"))
      (node (ref "R78") (pin "1") (pinfunction "1_1") (pintype "passive"))
      (node (ref "U23") (pin "4") (pinfunction "C_4") (pintype "passive"))
    )
    (net (code "16") (name "/INPUT4") (class "Default")
      (node (ref "*1") (pin "13") (pinfunction "PA3_13") (pintype "passive"))
      (node (ref "R79") (pin "1") (pinfunction "1_1") (pintype "passive"))
      (node (ref "U24") (pin "4") (pinfunction "C_4") (pintype "passive"))
    )
    (net (code "17") (name "/LS_XTAL1") (class "Default")
      (node (ref "*1") (pin "3") (pinfunction "PC14-OSC32_IN_3") (pintype "passive"))
      (node (ref "C1") (pin "1") (pinfunction "1_1") (pintype "passive"))
      (node (ref "U3") (pin "2") (pinfunction "OSC2_2") (pintype "passive"))
    )
    (net (code "18") (name "/LS_XTAL2") (class "Default")
      (node (ref "*1") (pin "4") (pinfunction "PC15-OSC32_OUT_4") (pintype "passive"))
      (node (ref "C7") (pin "1") (pinfunction "1_1") (pintype "passive"))
      (node (ref "U3") (pin "1") (pinfunction "OSC1_1") (pintype "passive"))
    )
    (net (code "19") (name "/NRST") (class "Default")
      (node (ref "*1") (pin "7") (pinfunction "NRST_7") (pintype "passive"))
      (node (ref "C20") (pin "1") (pinfunction "1_1") (pintype "passive"))
      (node (ref "JP5") (pin "1") (pinfunction "1_1") (pintype "passive"))
      (node (ref "R4") (pin "1") (pinfunction "1_1") (pintype "passive"))
      (node (ref "SW1") (pin "2") (pinfunction "2_2") (pintype "passive"))
    )
    (net (code "20") (name "/OPTO1") (class "Default")
      (node (ref "*1") (pin "18") (pinfunction "PB0_18") (pintype "passive"))
      (node (ref "U5") (pin "2") (pinfunction "K_2") (pintype "passive"))
    )
    (net (code "21") (name "/OPTO2") (class "Default")
      (node (ref "*1") (pin "19") (pinfunction "PB1_19") (pintype "passive"))
      (node (ref "U6") (pin "2") (pinfunction "K_2") (pintype "passive"))
    )
    (net (code "22") (name "/OPTO3") (class "Default")
      (node (ref "*1") (pin "21") (pinfunction "PB10_21") (pintype "passive"))
      (node (ref "U7") (pin "2") (pinfunction "K_2") (pintype "passive"))
    )
    (net (code "23") (name "/OPTO4") (class "Default")
      (node (ref "*1") (pin "22") (pinfunction "PB11_22") (pintype "passive"))
      (node (ref "U8") (pin "2") (pinfunction "K_2") (pintype "passive"))
    )
    (net (code "24") (name "/OPTO5") (class "Default")
      (node (ref "*1") (pin "25") (pinfunction "PB12_25") (pintype "passive"))
      (node (ref "U9") (pin "2") (pinfunction "K_2") (pintype "passive"))
    )
    (net (code "25") (name "/OPTO6") (class "Default")
      (node (ref "*1") (pin "26") (pinfunction "PB13_26") (pintype "passive"))
      (node (ref "U10") (pin "2") (pinfunction "K_2") (pintype "passive"))
    )
    (net (code "26") (name "/OPTO7") (class "Default")
      (node (ref "*1") (pin "27") (pinfunction "PB14_27") (pintype "passive"))
      (node (ref "U11") (pin "2") (pinfunction "K_2") (pintype "passive"))
    )
    (net (code "27") (name "/OPTO8") (class "Default")
      (node (ref "*1") (pin "28") (pinfunction "PB15_28") (pintype "passive"))
      (node (ref "U12") (pin "2") (pinfunction "K_2") (pintype "passive"))
    )
    (net (code "28") (name "/OPTO9") (class "Default")
      (node (ref "*1") (pin "29") (pinfunction "PA8_29") (pintype "passive"))
      (node (ref "U13") (pin "2") (pinfunction "K_2") (pintype "passive"))
    )
    (net (code "29") (name "/OPTO10") (class "Default")
      (node (ref "*1") (pin "38") (pinfunction "PA15_38") (pintype "passive"))
      (node (ref "U14") (pin "2") (pinfunction "K_2") (pintype "passive"))
    )
    (net (code "30") (name "/OPTO11") (class "Default")
      (node (ref "*1") (pin "39") (pinfunction "PB3_39") (pintype "passive"))
      (node (ref "U15") (pin "2") (pinfunction "K_2") (pintype "passive"))
    )
    (net (code "31") (name "/OPTO12") (class "Default")
      (node (ref "*1") (pin "40") (pinfunction "PB4_40") (pintype "passive"))
      (node (ref "U16") (pin "2") (pinfunction "K_2") (pintype "passive"))
    )
    (net (code "32") (name "/OPTO13") (class "Default")
      (node (ref "*1") (pin "41") (pinfunction "PB5_41") (pintype "passive"))
      (node (ref "U17") (pin "2") (pinfunction "K_2") (pintype "passive"))
    )
    (net (code "33") (name "/OPTO14") (class "Default")
      (node (ref "*1") (pin "45") (pinfunction "PB8_45") (pintype "passive"))
      (node (ref "U18") (pin "2") (pinfunction "K_2") (pintype "passive"))
    )
    (net (code "34") (name "/OPTO15") (class "Default")
      (node (ref "*1") (pin "46") (pinfunction "PB9_46") (pintype "passive"))
      (node (ref "U19") (pin "2") (pinfunction "K_2") (pintype "passive"))
    )
    (net (code "35") (name "/OPTO16") (class "Default")
      (node (ref "*1") (pin "2") (pinfunction "PC13-TAMPER-RTC_2") (pintype "passive"))
      (node (ref "U20") (pin "2") (pinfunction "K_2") (pintype "passive"))
    )
    (net (code "36") (name "/OP_OUT1") (class "Default")
      (node (ref "IC1") (pin "1") (pinfunction "I1_1") (pintype "input"))
      (node (ref "R16") (pin "1") (pinfunction "1_1") (pintype "passive"))
      (node (ref "U5") (pin "4") (pinfunction "C_4") (pintype "passive"))
    )
    (net (code "37") (name "/OP_OUT2") (class "Default")
      (node (ref "IC1") (pin "2") (pinfunction "I2_2") (pintype "input"))
      (node (ref "R17") (pin "1") (pinfunction "1_1") (pintype "passive"))
      (node (ref "U6") (pin "4") (pinfunction "C_4") (pintype "passive"))
    )
    (net (code "38") (name "/OP_OUT3") (class "Default")
      (node (ref "IC1") (pin "3") (pinfunction "I3_3") (pintype "input"))
      (node (ref "R18") (pin "1") (pinfunction "1_1") (pintype "passive"))
      (node (ref "U7") (pin "4") (pinfunction "C_4") (pintype "passive"))
    )
    (net (code "39") (name "/OP_OUT4") (class "Default")
      (node (ref "IC1") (pin "4") (pinfunction "I4_4") (pintype "input"))
      (node (ref "R19") (pin "1") (pinfunction "1_1") (pintype "passive"))
      (node (ref "U8") (pin "4") (pinfunction "C_4") (pintype "passive"))
    )
    (net (code "40") (name "/OP_OUT5") (class "Default")
      (node (ref "IC1") (pin "5") (pinfunction "I5_5") (pintype "input"))
      (node (ref "R20") (pin "1") (pinfunction "1_1") (pintype "passive"))
      (node (ref "U9") (pin "4") (pinfunction "C_4") (pintype "passive"))
    )
    (net (code "41") (name "/OP_OUT6") (class "Default")
      (node (ref "IC1") (pin "6") (pinfunction "I6_6") (pintype "input"))
      (node (ref "R21") (pin "1") (pinfunction "1_1") (pintype "passive"))
      (node (ref "U10") (pin "4") (pinfunction "C_4") (pintype "passive"))
    )
    (net (code "42") (name "/OP_OUT7") (class "Default")
      (node (ref "IC1") (pin "7") (pinfunction "I7_7") (pintype "input"))
      (node (ref "R22") (pin "1") (pinfunction "1_1") (pintype "passive"))
      (node (ref "U11") (pin "4") (pinfunction "C_4") (pintype "passive"))
    )
    (net (code "43") (name "/OP_OUT8") (class "Default")
      (node (ref "IC1") (pin "8") (pinfunction "I8_8") (pintype "input"))
      (node (ref "R23") (pin "1") (pinfunction "1_1") (pintype "passive"))
      (node (ref "U12") (pin "4") (pinfunction "C_4") (pintype "passive"))
    )
    (net (code "44") (name "/OP_OUT9") (class "Default")
      (node (ref "IC2") (pin "1") (pinfunction "I1_1") (pintype "input"))
      (node (ref "R32") (pin "1") (pinfunction "1_1") (pintype "passive"))
      (node (ref "U13") (pin "4") (pinfunction "C_4") (pintype "passive"))
    )
    (net (code "45") (name "/OP_OUT10") (class "Default")
      (node (ref "IC2") (pin "2") (pinfunction "I2_2") (pintype "input"))
      (node (ref "R33") (pin "1") (pinfunction "1_1") (pintype "passive"))
      (node (ref "U14") (pin "4") (pinfunction "C_4") (pintype "passive"))
    )
    (net (code "46") (name "/OP_OUT11") (class "Default")
      (node (ref "IC2") (pin "3") (pinfunction "I3_3") (pintype "input"))
      (node (ref "R34") (pin "1") (pinfunction "1_1") (pintype "passive"))
      (node (ref "U15") (pin "4") (pinfunction "C_4") (pintype "passive"))
    )
    (net (code "47") (name "/OP_OUT12") (class "Default")
      (node (ref "IC2") (pin "4") (pinfunction "I4_4") (pintype "input"))
      (node (ref "R35") (pin "1") (pinfunction "1_1") (pintype "passive"))
      (node (ref "U16") (pin "4") (pinfunction "C_4") (pintype "passive"))
    )
    (net (code "48") (name "/OP_OUT13") (class "Default")
      (node (ref "IC2") (pin "5") (pinfunction "I5_5") (pintype "input"))
      (node (ref "R36") (pin "1") (pinfunction "1_1") (pintype "passive"))
      (node (ref "U17") (pin "4") (pinfunction "C_4") (pintype "passive"))
    )
    (net (code "49") (name "/OP_OUT14") (class "Default")
      (node (ref "IC2") (pin "6") (pinfunction "I6_6") (pintype "input"))
      (node (ref "R37") (pin "1") (pinfunction "1_1") (pintype "passive"))
      (node (ref "U18") (pin "4") (pinfunction "C_4") (pintype "passive"))
    )
    (net (code "50") (name "/OP_OUT15") (class "Default")
      (node (ref "IC2") (pin "7") (pinfunction "I7_7") (pintype "input"))
      (node (ref "R38") (pin "1") (pinfunction "1_1") (pintype "passive"))
      (node (ref "U19") (pin "4") (pinfunction "C_4") (pintype "passive"))
    )
    (net (code "51") (name "/OP_OUT16") (class "Default")
      (node (ref "IC2") (pin "8") (pinfunction "I8_8") (pintype "input"))
      (node (ref "R39") (pin "1") (pinfunction "1_1") (pintype "passive"))
      (node (ref "U20") (pin "4") (pinfunction "C_4") (pintype "passive"))
    )
    (net (code "52") (name "/SPI_CS") (class "Default")
      (node (ref "*1") (pin "14") (pinfunction "PA4_14") (pintype "passive"))
      (node (ref "JP1") (pin "2") (pinfunction "2_2") (pintype "passive"))
    )
    (net (code "53") (name "/SPI_MISO") (class "Default")
      (node (ref "*1") (pin "16") (pinfunction "PA6_16") (pintype "passive"))
      (node (ref "JP1") (pin "4") (pinfunction "4_4") (pintype "passive"))
    )
    (net (code "54") (name "/SPI_MOSI") (class "Default")
      (node (ref "*1") (pin "17") (pinfunction "PA7_17") (pintype "passive"))
      (node (ref "JP1") (pin "3") (pinfunction "3_3") (pintype "passive"))
    )
    (net (code "55") (name "/SPI_SCK") (class "Default")
      (node (ref "*1") (pin "15") (pinfunction "PA5_15") (pintype "passive"))
      (node (ref "JP1") (pin "5") (pinfunction "5_5") (pintype "passive"))
    )
    (net (code "56") (name "/SWCK") (class "Default")
      (node (ref "*1") (pin "37") (pinfunction "PA14_37") (pintype "passive"))
      (node (ref "JP5") (pin "3") (pinfunction "3_3") (pintype "passive"))
    )
    (net (code "57") (name "/SWDO") (class "Default")
      (node (ref "*1") (pin "34") (pinfunction "PA13_34") (pintype "passive"))
      (node (ref "JP5") (pin "2") (pinfunction "2_2") (pintype "passive"))
    )
    (net (code "58") (name "/UART_RX") (class "Default")
      (node (ref "*1") (pin "31") (pinfunction "PA10_31") (pintype "passive"))
      (node (ref "JP3") (pin "3") (pinfunction "3_3") (pintype "passive"))
    )
    (net (code "59") (name "/UART_TX") (class "Default")
      (node (ref "*1") (pin "30") (pinfunction "PA9_30") (pintype "passive"))
      (node (ref "JP3") (pin "2") (pinfunction "2_2") (pintype "passive"))
    )
    (net (code "60") (name "/ULN_OUT1") (class "Default")
      (node (ref "D2") (pin "1") (pinfunction "A_1") (pintype "passive"))
      (node (ref "D8") (pin "2") (pinfunction "K_2") (pintype "passive"))
      (node (ref "IC1") (pin "18") (pinfunction "O1_18") (pintype "open_collector"))
      (node (ref "R46") (pin "1") (pinfunction "1_1") (pintype "passive"))
      (node (ref "RL1") (pin "4") (pinfunction "4_4") (pintype "passive"))
    )
    (net (code "61") (name "/ULN_OUT2") (class "Default")
      (node (ref "D3") (pin "1") (pinfunction "A_1") (pintype "passive"))
      (node (ref "D9") (pin "2") (pinfunction "K_2") (pintype "passive"))
      (node (ref "IC1") (pin "17") (pinfunction "O2_17") (pintype "open_collector"))
      (node (ref "R47") (pin "1") (pinfunction "1_1") (pintype "passive"))
      (node (ref "RL2") (pin "4") (pinfunction "4_4") (pintype "passive"))
    )
    (net (code "62") (name "/ULN_OUT3") (class "Default")
      (node (ref "D10") (pin "2") (pinfunction "K_2") (pintype "passive"))
      (node (ref "D4") (pin "1") (pinfunction "A_1") (pintype "passive"))
      (node (ref "IC1") (pin "16") (pinfunction "O3_16") (pintype "open_collector"))
      (node (ref "R48") (pin "1") (pinfunction "1_1") (pintype "passive"))
      (node (ref "RL3") (pin "4") (pinfunction "4_4") (pintype "passive"))
    )
    (net (code "63") (name "/ULN_OUT4") (class "Default")
      (node (ref "D11") (pin "2") (pinfunction "K_2") (pintype "passive"))
      (node (ref "D5") (pin "1") (pinfunction "A_1") (pintype "passive"))
      (node (ref "IC1") (pin "15") (pinfunction "O4_15") (pintype "open_collector"))
      (node (ref "R49") (pin "1") (pinfunction "1_1") (pintype "passive"))
      (node (ref "RL4") (pin "4") (pinfunction "4_4") (pintype "passive"))
    )
    (net (code "64") (name "/ULN_OUT5") (class "Default")
      (node (ref "D12") (pin "2") (pinfunction "K_2") (pintype "passive"))
      (node (ref "D6") (pin "1") (pinfunction "A_1") (pintype "passive"))
      (node (ref "IC1") (pin "14") (pinfunction "O5_14") (pintype "open_collector"))
      (node (ref "R50") (pin "1") (pinfunction "1_1") (pintype "passive"))
      (node (ref "RL5") (pin "4") (pinfunction "4_4") (pintype "passive"))
    )
    (net (code "65") (name "/ULN_OUT6") (class "Default")
      (node (ref "D13") (pin "2") (pinfunction "K_2") (pintype "passive"))
      (node (ref "D7") (pin "1") (pinfunction "A_1") (pintype "passive"))
      (node (ref "IC1") (pin "13") (pinfunction "O6_13") (pintype "open_collector"))
      (node (ref "R51") (pin "1") (pinfunction "1_1") (pintype "passive"))
      (node (ref "RL6") (pin "4") (pinfunction "4_4") (pintype "passive"))
    )
    (net (code "66") (name "/ULN_OUT7") (class "Default")
      (node (ref "D14") (pin "1") (pinfunction "A_1") (pintype "passive"))
      (node (ref "D20") (pin "2") (pinfunction "K_2") (pintype "passive"))
      (node (ref "IC1") (pin "12") (pinfunction "O7_12") (pintype "open_collector"))
      (node (ref "R58") (pin "1") (pinfunction "1_1") (pintype "passive"))
      (node (ref "RL7") (pin "4") (pinfunction "4_4") (pintype "passive"))
    )
    (net (code "67") (name "/ULN_OUT8") (class "Default")
      (node (ref "D15") (pin "1") (pinfunction "A_1") (pintype "passive"))
      (node (ref "D21") (pin "2") (pinfunction "K_2") (pintype "passive"))
      (node (ref "IC1") (pin "11") (pinfunction "O8_11") (pintype "open_collector"))
      (node (ref "R59") (pin "1") (pinfunction "1_1") (pintype "passive"))
      (node (ref "RL8") (pin "4") (pinfunction "4_4") (pintype "passive"))
    )
    (net (code "68") (name "/ULN_OUT9") (class "Default")
      (node (ref "D16") (pin "1") (pinfunction "A_1") (pintype "passive"))
      (node (ref "D22") (pin "2") (pinfunction "K_2") (pintype "passive"))
      (node (ref "IC2") (pin "18") (pinfunction "O1_18") (pintype "open_collector"))
      (node (ref "R60") (pin "1") (pinfunction "1_1") (pintype "passive"))
      (node (ref "RL9") (pin "4") (pinfunction "4_4") (pintype "passive"))
    )
    (net (code "69") (name "/ULN_OUT10") (class "Default")
      (node (ref "D17") (pin "1") (pinfunction "A_1") (pintype "passive"))
      (node (ref "D23") (pin "2") (pinfunction "K_2") (pintype "passive"))
      (node (ref "IC2") (pin "17") (pinfunction "O2_17") (pintype "open_collector"))
      (node (ref "R61") (pin "1") (pinfunction "1_1") (pintype "passive"))
      (node (ref "RL10") (pin "4") (pinfunction "4_4") (pintype "passive"))
    )
    (net (code "70") (name "/ULN_OUT11") (class "Default")
      (node (ref "D18") (pin "1") (pinfunction "A_1") (pintype "passive"))
      (node (ref "D24") (pin "2") (pinfunction "K_2") (pintype "passive"))
      (node (ref "IC2") (pin "16") (pinfunction "O3_16") (pintype "open_collector"))
      (node (ref "R62") (pin "1") (pinfunction "1_1") (pintype "passive"))
      (node (ref "RL11") (pin "4") (pinfunction "4_4") (pintype "passive"))
    )
    (net (code "71") (name "/ULN_OUT12") (class "Default")
      (node (ref "D19") (pin "1") (pinfunction "A_1") (pintype "passive"))
      (node (ref "D25") (pin "2") (pinfunction "K_2") (pintype "passive"))
      (node (ref "IC2") (pin "15") (pinfunction "O4_15") (pintype "open_collector"))
      (node (ref "R63") (pin "1") (pinfunction "1_1") (pintype "passive"))
      (node (ref "RL12") (pin "4") (pinfunction "4_4") (pintype "passive"))
    )
    (net (code "72") (name "/ULN_OUT13") (class "Default")
      (node (ref "D26") (pin "1") (pinfunction "A_1") (pintype "passive"))
      (node (ref "D30") (pin "2") (pinfunction "K_2") (pintype "passive"))
      (node (ref "IC2") (pin "14") (pinfunction "O5_14") (pintype "open_collector"))
      (node (ref "R68") (pin "1") (pinfunction "1_1") (pintype "passive"))
      (node (ref "RL13") (pin "4") (pinfunction "4_4") (pintype "passive"))
    )
    (net (code "73") (name "/ULN_OUT14") (class "Default")
      (node (ref "D27") (pin "1") (pinfunction "A_1") (pintype "passive"))
      (node (ref "D31") (pin "2") (pinfunction "K_2") (pintype "passive"))
      (node (ref "IC2") (pin "13") (pinfunction "O6_13") (pintype "open_collector"))
      (node (ref "R69") (pin "1") (pinfunction "1_1") (pintype "passive"))
      (node (ref "RL14") (pin "4") (pinfunction "4_4") (pintype "passive"))
    )
    (net (code "74") (name "/ULN_OUT15") (class "Default")
      (node (ref "D28") (pin "1") (pinfunction "A_1") (pintype "passive"))
      (node (ref "D32") (pin "2") (pinfunction "K_2") (pintype "passive"))
      (node (ref "IC2") (pin "12") (pinfunction "O7_12") (pintype "open_collector"))
      (node (ref "R70") (pin "1") (pinfunction "1_1") (pintype "passive"))
      (node (ref "RL15") (pin "4") (pinfunction "4_4") (pintype "passive"))
    )
    (net (code "75") (name "/ULN_OUT16") (class "Default")
      (node (ref "D29") (pin "1") (pinfunction "A_1") (pintype "passive"))
      (node (ref "D33") (pin "2") (pinfunction "K_2") (pintype "passive"))
      (node (ref "IC2") (pin "11") (pinfunction "O8_11") (pintype "open_collector"))
      (node (ref "R71") (pin "1") (pinfunction "1_1") (pintype "passive"))
      (node (ref "RL16") (pin "4") (pinfunction "4_4") (pintype "passive"))
    )
    (net (code "76") (name "/VBAT") (class "Default")
      (node (ref "*1") (pin "1") (pinfunction "VBAT_1") (pintype "passive"))
      (node (ref "BT1") (pin "1") (pinfunction "+3V_1") (pintype "passive"))
    )
    (net (code "77") (name "3.3V_ISO") (class "Default")
      (node (ref "*1") (pin "24") (pinfunction "VDD_1_24") (pintype "passive"))
      (node (ref "*1") (pin "36") (pinfunction "VDD_2_36") (pintype "passive"))
      (node (ref "*1") (pin "48") (pinfunction "VDD_3_48") (pintype "passive"))
      (node (ref "*1") (pin "9") (pinfunction "VDDA_9") (pintype "passive"))
      (node (ref "C11") (pin "1") (pinfunction "1_1") (pintype "passive"))
      (node (ref "C12") (pin "1") (pinfunction "1_1") (pintype "passive"))
      (node (ref "C13") (pin "1") (pinfunction "1_1") (pintype "passive"))
      (node (ref "C14") (pin "1") (pinfunction "1_1") (pintype "passive"))
      (node (ref "C15") (pin "1") (pinfunction "1_1") (pintype "passive"))
      (node (ref "C16") (pin "1") (pinfunction "1_1") (pintype "passive"))
      (node (ref "C17") (pin "1") (pinfunction "1_1") (pintype "passive"))
      (node (ref "C18") (pin "1") (pinfunction "1_1") (pintype "passive"))
      (node (ref "C19") (pin "1") (pinfunction "1_1") (pintype "passive"))
      (node (ref "C2") (pin "1") (pinfunction "1_1") (pintype "passive"))
      (node (ref "C3") (pin "1") (pinfunction "1_1") (pintype "passive"))
      (node (ref "C5") (pin "2") (pinfunction "2_2") (pintype "passive"))
      (node (ref "JP1") (pin "1") (pinfunction "1_1") (pintype "passive"))
      (node (ref "JP2") (pin "1") (pinfunction "1_1") (pintype "passive"))
      (node (ref "JP3") (pin "1") (pinfunction "1_1") (pintype "passive"))
      (node (ref "R1") (pin "2") (pinfunction "2_2") (pintype "passive"))
      (node (ref "R3") (pin "2") (pinfunction "2_2") (pintype "passive"))
      (node (ref "R4") (pin "2") (pinfunction "2_2") (pintype "passive"))
      (node (ref "R5") (pin "2") (pinfunction "2_2") (pintype "passive"))
      (node (ref "R6") (pin "2") (pinfunction "2_2") (pintype "passive"))
      (node (ref "R7") (pin "2") (pinfunction "2_2") (pintype "passive"))
      (node (ref "R76") (pin "2") (pinfunction "2_2") (pintype "passive"))
      (node (ref "R77") (pin "2") (pinfunction "2_2") (pintype "passive"))
      (node (ref "R78") (pin "2") (pinfunction "2_2") (pintype "passive"))
      (node (ref "R79") (pin "2") (pinfunction "2_2") (pintype "passive"))
      (node (ref "U1") (pin "2") (pinfunction "Vout_2") (pintype "passive"))
      (node (ref "U2") (pin "3") (pinfunction "VCC_3") (pintype "passive"))
    )
    (net (code "78") (name "GND") (class "Default")
      (node (ref "*2") (pin "1") (pinfunction "GND1_1") (pintype "passive"))
      (node (ref "C8") (pin "2") (pinfunction "2_2") (pintype "passive"))
      (node (ref "HD18") (pin "1") (pinfunction "1_1") (pintype "passive"))
      (node (ref "IC1") (pin "9") (pinfunction "GND_9") (pintype "power_in"))
      (node (ref "IC2") (pin "9") (pinfunction "GND_9") (pintype "power_in"))
      (node (ref "JP4") (pin "6") (pinfunction "6_6") (pintype "passive"))
      (node (ref "U10") (pin "3") (pinfunction "E_3") (pintype "passive"))
      (node (ref "U11") (pin "3") (pinfunction "E_3") (pintype "passive"))
      (node (ref "U12") (pin "3") (pinfunction "E_3") (pintype "passive"))
      (node (ref "U13") (pin "3") (pinfunction "E_3") (pintype "passive"))
      (node (ref "U14") (pin "3") (pinfunction "E_3") (pintype "passive"))
      (node (ref "U15") (pin "3") (pinfunction "E_3") (pintype "passive"))
      (node (ref "U16") (pin "3") (pinfunction "E_3") (pintype "passive"))
      (node (ref "U17") (pin "3") (pinfunction "E_3") (pintype "passive"))
      (node (ref "U18") (pin "3") (pinfunction "E_3") (pintype "passive"))
      (node (ref "U19") (pin "3") (pinfunction "E_3") (pintype "passive"))
      (node (ref "U20") (pin "3") (pinfunction "E_3") (pintype "passive"))
      (node (ref "U5") (pin "3") (pinfunction "E_3") (pintype "passive"))
      (node (ref "U6") (pin "3") (pinfunction "E_3") (pintype "passive"))
      (node (ref "U7") (pin "3") (pinfunction "E_3") (pintype "passive"))
      (node (ref "U8") (pin "3") (pinfunction "E_3") (pintype "passive"))
      (node (ref "U9") (pin "3") (pinfunction "E_3") (pintype "passive"))
    )
    (net (code "79") (name "GND_ISO") (class "Default")
      (node (ref "*1") (pin "23") (pinfunction "VSS_1_23") (pintype "passive"))
      (node (ref "*1") (pin "35") (pinfunction "VSS_2_35") (pintype "passive"))
      (node (ref "*1") (pin "47") (pinfunction "VSS_3_47") (pintype "passive"))
      (node (ref "*1") (pin "8") (pinfunction "VSSA_8") (pintype "passive"))
      (node (ref "*2") (pin "3") (pinfunction "0V_3") (pintype "passive"))
      (node (ref "BT1") (pin "2") (pinfunction "GND_2") (pintype "passive"))
      (node (ref "C1") (pin "2") (pinfunction "2_2") (pintype "passive"))
      (node (ref "C10") (pin "2") (pinfunction "2_2") (pintype "passive"))
      (node (ref "C11") (pin "2") (pinfunction "2_2") (pintype "passive"))
      (node (ref "C12") (pin "2") (pinfunction "2_2") (pintype "passive"))
      (node (ref "C13") (pin "2") (pinfunction "2_2") (pintype "passive"))
      (node (ref "C14") (pin "2") (pinfunction "2_2") (pintype "passive"))
      (node (ref "C15") (pin "2") (pinfunction "2_2") (pintype "passive"))
      (node (ref "C16") (pin "2") (pinfunction "2_2") (pintype "passive"))
      (node (ref "C17") (pin "2") (pinfunction "2_2") (pintype "passive"))
      (node (ref "C18") (pin "2") (pinfunction "2_2") (pintype "passive"))
      (node (ref "C19") (pin "2") (pinfunction "2_2") (pintype "passive"))
      (node (ref "C2") (pin "2") (pinfunction "2_2") (pintype "passive"))
      (node (ref "C20") (pin "2") (pinfunction "2_2") (pintype "passive"))
      (node (ref "C3") (pin "2") (pinfunction "2_2") (pintype "passive"))
      (node (ref "C4") (pin "2") (pinfunction "2_2") (pintype "passive"))
      (node (ref "C5") (pin "1") (pinfunction "1_1") (pintype "passive"))
      (node (ref "C6") (pin "2") (pinfunction "2_2") (pintype "passive"))
      (node (ref "C7") (pin "2") (pinfunction "2_2") (pintype "passive"))
      (node (ref "C9") (pin "2") (pinfunction "2_2") (pintype "passive"))
      (node (ref "D1") (pin "2") (pinfunction "K_2") (pintype "passive"))
      (node (ref "JP1") (pin "6") (pinfunction "6_6") (pintype "passive"))
      (node (ref "JP2") (pin "4") (pinfunction "4_4") (pintype "passive"))
      (node (ref "JP3") (pin "4") (pinfunction "4_4") (pintype "passive"))
      (node (ref "JP5") (pin "4") (pinfunction "4_4") (pintype "passive"))
      (node (ref "P1") (pin "2") (pinfunction "2_2") (pintype "passive"))
      (node (ref "P2") (pin "2") (pinfunction "2_2") (pintype "passive"))
      (node (ref "SW1") (pin "1") (pinfunction "1_1") (pintype "passive"))
      (node (ref "U1") (pin "1") (pinfunction "GND_1") (pintype "passive"))
      (node (ref "U2") (pin "2") (pinfunction "GND_2") (pintype "passive"))
      (node (ref "U2") (pin "8") (pinfunction "RS_8") (pintype "passive"))
      (node (ref "U21") (pin "3") (pinfunction "E_3") (pintype "passive"))
      (node (ref "U22") (pin "3") (pinfunction "E_3") (pintype "passive"))
      (node (ref "U23") (pin "3") (pinfunction "E_3") (pintype "passive"))
      (node (ref "U24") (pin "3") (pinfunction "E_3") (pintype "passive"))
    )
    (net (code "80") (name "Net-(D1-A)") (class "Default")
      (node (ref "D1") (pin "1") (pinfunction "A_1") (pintype "passive"))
      (node (ref "R1") (pin "1") (pinfunction "1_1") (pintype "passive"))
    )
    (net (code "81") (name "Net-(D8-A)") (class "Default")
      (node (ref "D8") (pin "1") (pinfunction "A_1") (pintype "passive"))
      (node (ref "R40") (pin "1") (pinfunction "1_1") (pintype "passive"))
    )
    (net (code "82") (name "Net-(D9-A)") (class "Default")
      (node (ref "D9") (pin "1") (pinfunction "A_1") (pintype "passive"))
      (node (ref "R41") (pin "1") (pinfunction "1_1") (pintype "passive"))
    )
    (net (code "83") (name "Net-(D10-A)") (class "Default")
      (node (ref "D10") (pin "1") (pinfunction "A_1") (pintype "passive"))
      (node (ref "R42") (pin "1") (pinfunction "1_1") (pintype "passive"))
    )
    (net (code "84") (name "Net-(D11-A)") (class "Default")
      (node (ref "D11") (pin "1") (pinfunction "A_1") (pintype "passive"))
      (node (ref "R43") (pin "1") (pinfunction "1_1") (pintype "passive"))
    )
    (net (code "85") (name "Net-(D12-A)") (class "Default")
      (node (ref "D12") (pin "1") (pinfunction "A_1") (pintype "passive"))
      (node (ref "R44") (pin "1") (pinfunction "1_1") (pintype "passive"))
    )
    (net (code "86") (name "Net-(D13-A)") (class "Default")
      (node (ref "D13") (pin "1") (pinfunction "A_1") (pintype "passive"))
      (node (ref "R45") (pin "1") (pinfunction "1_1") (pintype "passive"))
    )
    (net (code "87") (name "Net-(D20-A)") (class "Default")
      (node (ref "D20") (pin "1") (pinfunction "A_1") (pintype "passive"))
      (node (ref "R52") (pin "1") (pinfunction "1_1") (pintype "passive"))
    )
    (net (code "88") (name "Net-(D21-A)") (class "Default")
      (node (ref "D21") (pin "1") (pinfunction "A_1") (pintype "passive"))
      (node (ref "R53") (pin "1") (pinfunction "1_1") (pintype "passive"))
    )
    (net (code "89") (name "Net-(D22-A)") (class "Default")
      (node (ref "D22") (pin "1") (pinfunction "A_1") (pintype "passive"))
      (node (ref "R54") (pin "1") (pinfunction "1_1") (pintype "passive"))
    )
    (net (code "90") (name "Net-(D23-A)") (class "Default")
      (node (ref "D23") (pin "1") (pinfunction "A_1") (pintype "passive"))
      (node (ref "R55") (pin "1") (pinfunction "1_1") (pintype "passive"))
    )
    (net (code "91") (name "Net-(D24-A)") (class "Default")
      (node (ref "D24") (pin "1") (pinfunction "A_1") (pintype "passive"))
      (node (ref "R56") (pin "1") (pinfunction "1_1") (pintype "passive"))
    )
    (net (code "92") (name "Net-(D25-A)") (class "Default")
      (node (ref "D25") (pin "1") (pinfunction "A_1") (pintype "passive"))
      (node (ref "R57") (pin "1") (pinfunction "1_1") (pintype "passive"))
    )
    (net (code "93") (name "Net-(D30-A)") (class "Default")
      (node (ref "D30") (pin "1") (pinfunction "A_1") (pintype "passive"))
      (node (ref "R64") (pin "1") (pinfunction "1_1") (pintype "passive"))
    )
    (net (code "94") (name "Net-(D31-A)") (class "Default")
      (node (ref "D31") (pin "1") (pinfunction "A_1") (pintype "passive"))
      (node (ref "R65") (pin "1") (pinfunction "1_1") (pintype "passive"))
    )
    (net (code "95") (name "Net-(D32-A)") (class "Default")
      (node (ref "D32") (pin "1") (pinfunction "A_1") (pintype "passive"))
      (node (ref "R66") (pin "1") (pinfunction "1_1") (pintype "passive"))
    )
    (net (code "96") (name "Net-(D33-A)") (class "Default")
      (node (ref "D33") (pin "1") (pinfunction "A_1") (pintype "passive"))
      (node (ref "R67") (pin "1") (pinfunction "1_1") (pintype "passive"))
    )
    (net (code "97") (name "Net-(HD2-Pad1)") (class "Default")
      (node (ref "HD2") (pin "1") (pinfunction "1_1") (pintype "passive"))
      (node (ref "RL1") (pin "2") (pinfunction "2_2") (pintype "passive"))
    )
    (net (code "98") (name "Net-(HD2-Pad2)") (class "Default")
      (node (ref "HD2") (pin "2") (pinfunction "2_2") (pintype "passive"))
      (node (ref "RL1") (pin "5") (pinfunction "5_5") (pintype "passive"))
    )
    (net (code "99") (name "Net-(HD2-Pad3)") (class "Default")
      (node (ref "HD2") (pin "3") (pinfunction "3_3") (pintype "passive"))
      (node (ref "RL1") (pin "1") (pinfunction "1_1") (pintype "passive"))
    )
    (net (code "100") (name "Net-(HD3-Pad1)") (class "Default")
      (node (ref "HD3") (pin "1") (pinfunction "1_1") (pintype "passive"))
      (node (ref "RL2") (pin "2") (pinfunction "2_2") (pintype "passive"))
    )
    (net (code "101") (name "Net-(HD3-Pad2)") (class "Default")
      (node (ref "HD3") (pin "2") (pinfunction "2_2") (pintype "passive"))
      (node (ref "RL2") (pin "5") (pinfunction "5_5") (pintype "passive"))
    )
    (net (code "102") (name "Net-(HD3-Pad3)") (class "Default")
      (node (ref "HD3") (pin "3") (pinfunction "3_3") (pintype "passive"))
      (node (ref "RL2") (pin "1") (pinfunction "1_1") (pintype "passive"))
    )
    (net (code "103") (name "Net-(HD4-Pad1)") (class "Default")
      (node (ref "HD4") (pin "1") (pinfunction "1_1") (pintype "passive"))
      (node (ref "RL3") (pin "2") (pinfunction "2_2") (pintype "passive"))
    )
    (net (code "104") (name "Net-(HD4-Pad2)") (class "Default")
      (node (ref "HD4") (pin "2") (pinfunction "2_2") (pintype "passive"))
      (node (ref "RL3") (pin "5") (pinfunction "5_5") (pintype "passive"))
    )
    (net (code "105") (name "Net-(HD4-Pad3)") (class "Default")
      (node (ref "HD4") (pin "3") (pinfunction "3_3") (pintype "passive"))
      (node (ref "RL3") (pin "1") (pinfunction "1_1") (pintype "passive"))
    )
    (net (code "106") (name "Net-(HD5-Pad1)") (class "Default")
      (node (ref "HD5") (pin "1") (pinfunction "1_1") (pintype "passive"))
      (node (ref "RL4") (pin "2") (pinfunction "2_2") (pintype "passive"))
    )
    (net (code "107") (name "Net-(HD5-Pad2)") (class "Default")
      (node (ref "HD5") (pin "2") (pinfunction "2_2") (pintype "passive"))
      (node (ref "RL4") (pin "5") (pinfunction "5_5") (pintype "passive"))
    )
    (net (code "108") (name "Net-(HD5-Pad3)") (class "Default")
      (node (ref "HD5") (pin "3") (pinfunction "3_3") (pintype "passive"))
      (node (ref "RL4") (pin "1") (pinfunction "1_1") (pintype "passive"))
    )
    (net (code "109") (name "Net-(HD6-Pad1)") (class "Default")
      (node (ref "HD6") (pin "1") (pinfunction "1_1") (pintype "passive"))
      (node (ref "RL5") (pin "2") (pinfunction "2_2") (pintype "passive"))
    )
    (net (code "110") (name "Net-(HD6-Pad2)") (class "Default")
      (node (ref "HD6") (pin "2") (pinfunction "2_2") (pintype "passive"))
      (node (ref "RL5") (pin "5") (pinfunction "5_5") (pintype "passive"))
    )
    (net (code "111") (name "Net-(HD6-Pad3)") (class "Default")
      (node (ref "HD6") (pin "3") (pinfunction "3_3") (pintype "passive"))
      (node (ref "RL5") (pin "1") (pinfunction "1_1") (pintype "passive"))
    )
    (net (code "112") (name "Net-(HD7-Pad1)") (class "Default")
      (node (ref "HD7") (pin "1") (pinfunction "1_1") (pintype "passive"))
      (node (ref "RL6") (pin "2") (pinfunction "2_2") (pintype "passive"))
    )
    (net (code "113") (name "Net-(HD7-Pad2)") (class "Default")
      (node (ref "HD7") (pin "2") (pinfunction "2_2") (pintype "passive"))
      (node (ref "RL6") (pin "5") (pinfunction "5_5") (pintype "passive"))
    )
    (net (code "114") (name "Net-(HD7-Pad3)") (class "Default")
      (node (ref "HD7") (pin "3") (pinfunction "3_3") (pintype "passive"))
      (node (ref "RL6") (pin "1") (pinfunction "1_1") (pintype "passive"))
    )
    (net (code "115") (name "Net-(HD8-Pad1)") (class "Default")
      (node (ref "HD8") (pin "1") (pinfunction "1_1") (pintype "passive"))
      (node (ref "RL7") (pin "2") (pinfunction "2_2") (pintype "passive"))
    )
    (net (code "116") (name "Net-(HD8-Pad2)") (class "Default")
      (node (ref "HD8") (pin "2") (pinfunction "2_2") (pintype "passive"))
      (node (ref "RL7") (pin "5") (pinfunction "5_5") (pintype "passive"))
    )
    (net (code "117") (name "Net-(HD8-Pad3)") (class "Default")
      (node (ref "HD8") (pin "3") (pinfunction "3_3") (pintype "passive"))
      (node (ref "RL7") (pin "1") (pinfunction "1_1") (pintype "passive"))
    )
    (net (code "118") (name "Net-(HD9-Pad1)") (class "Default")
      (node (ref "HD9") (pin "1") (pinfunction "1_1") (pintype "passive"))
      (node (ref "RL8") (pin "2") (pinfunction "2_2") (pintype "passive"))
    )
    (net (code "119") (name "Net-(HD9-Pad2)") (class "Default")
      (node (ref "HD9") (pin "2") (pinfunction "2_2") (pintype "passive"))
      (node (ref "RL8") (pin "5") (pinfunction "5_5") (pintype "passive"))
    )
    (net (code "120") (name "Net-(HD9-Pad3)") (class "Default")
      (node (ref "HD9") (pin "3") (pinfunction "3_3") (pintype "passive"))
      (node (ref "RL8") (pin "1") (pinfunction "1_1") (pintype "passive"))
    )
    (net (code "121") (name "Net-(HD10-Pad1)") (class "Default")
      (node (ref "HD10") (pin "1") (pinfunction "1_1") (pintype "passive"))
      (node (ref "RL9") (pin "2") (pinfunction "2_2") (pintype "passive"))
    )
    (net (code "122") (name "Net-(HD10-Pad2)") (class "Default")
      (node (ref "HD10") (pin "2") (pinfunction "2_2") (pintype "passive"))
      (node (ref "RL9") (pin "5") (pinfunction "5_5") (pintype "passive"))
    )
    (net (code "123") (name "Net-(HD10-Pad3)") (class "Default")
      (node (ref "HD10") (pin "3") (pinfunction "3_3") (pintype "passive"))
      (node (ref "RL9") (pin "1") (pinfunction "1_1") (pintype "passive"))
    )
    (net (code "124") (name "Net-(HD11-Pad1)") (class "Default")
      (node (ref "HD11") (pin "1") (pinfunction "1_1") (pintype "passive"))
      (node (ref "RL10") (pin "2") (pinfunction "2_2") (pintype "passive"))
    )
    (net (code "125") (name "Net-(HD11-Pad2)") (class "Default")
      (node (ref "HD11") (pin "2") (pinfunction "2_2") (pintype "passive"))
      (node (ref "RL10") (pin "5") (pinfunction "5_5") (pintype "passive"))
    )
    (net (code "126") (name "Net-(HD11-Pad3)") (class "Default")
      (node (ref "HD11") (pin "3") (pinfunction "3_3") (pintype "passive"))
      (node (ref "RL10") (pin "1") (pinfunction "1_1") (pintype "passive"))
    )
    (net (code "127") (name "Net-(HD12-Pad1)") (class "Default")
      (node (ref "HD12") (pin "1") (pinfunction "1_1") (pintype "passive"))
      (node (ref "RL11") (pin "2") (pinfunction "2_2") (pintype "passive"))
    )
    (net (code "128") (name "Net-(HD12-Pad2)") (class "Default")
      (node (ref "HD12") (pin "2") (pinfunction "2_2") (pintype "passive"))
      (node (ref "RL11") (pin "5") (pinfunction "5_5") (pintype "passive"))
    )
    (net (code "129") (name "Net-(HD12-Pad3)") (class "Default")
      (node (ref "HD12") (pin "3") (pinfunction "3_3") (pintype "passive"))
      (node (ref "RL11") (pin "1") (pinfunction "1_1") (pintype "passive"))
    )
    (net (code "130") (name "Net-(HD13-Pad1)") (class "Default")
      (node (ref "HD13") (pin "1") (pinfunction "1_1") (pintype "passive"))
      (node (ref "RL12") (pin "2") (pinfunction "2_2") (pintype "passive"))
    )
    (net (code "131") (name "Net-(HD13-Pad2)") (class "Default")
      (node (ref "HD13") (pin "2") (pinfunction "2_2") (pintype "passive"))
      (node (ref "RL12") (pin "5") (pinfunction "5_5") (pintype "passive"))
    )
    (net (code "132") (name "Net-(HD13-Pad3)") (class "Default")
      (node (ref "HD13") (pin "3") (pinfunction "3_3") (pintype "passive"))
      (node (ref "RL12") (pin "1") (pinfunction "1_1") (pintype "passive"))
    )
    (net (code "133") (name "Net-(HD14-Pad1)") (class "Default")
      (node (ref "HD14") (pin "1") (pinfunction "1_1") (pintype "passive"))
      (node (ref "RL13") (pin "2") (pinfunction "2_2") (pintype "passive"))
    )
    (net (code "134") (name "Net-(HD14-Pad2)") (class "Default")
      (node (ref "HD14") (pin "2") (pinfunction "2_2") (pintype "passive"))
      (node (ref "RL13") (pin "5") (pinfunction "5_5") (pintype "passive"))
    )
    (net (code "135") (name "Net-(HD14-Pad3)") (class "Default")
      (node (ref "HD14") (pin "3") (pinfunction "3_3") (pintype "passive"))
      (node (ref "RL13") (pin "1") (pinfunction "1_1") (pintype "passive"))
    )
    (net (code "136") (name "Net-(HD15-Pad1)") (class "Default")
      (node (ref "HD15") (pin "1") (pinfunction "1_1") (pintype "passive"))
      (node (ref "RL14") (pin "2") (pinfunction "2_2") (pintype "passive"))
    )
    (net (code "137") (name "Net-(HD15-Pad2)") (class "Default")
      (node (ref "HD15") (pin "2") (pinfunction "2_2") (pintype "passive"))
      (node (ref "RL14") (pin "5") (pinfunction "5_5") (pintype "passive"))
    )
    (net (code "138") (name "Net-(HD15-Pad3)") (class "Default")
      (node (ref "HD15") (pin "3") (pinfunction "3_3") (pintype "passive"))
      (node (ref "RL14") (pin "1") (pinfunction "1_1") (pintype "passive"))
    )
    (net (code "139") (name "Net-(HD16-Pad1)") (class "Default")
      (node (ref "HD16") (pin "1") (pinfunction "1_1") (pintype "passive"))
      (node (ref "RL15") (pin "2") (pinfunction "2_2") (pintype "passive"))
    )
    (net (code "140") (name "Net-(HD16-Pad2)") (class "Default")
      (node (ref "HD16") (pin "2") (pinfunction "2_2") (pintype "passive"))
      (node (ref "RL15") (pin "5") (pinfunction "5_5") (pintype "passive"))
    )
    (net (code "141") (name "Net-(HD16-Pad3)") (class "Default")
      (node (ref "HD16") (pin "3") (pinfunction "3_3") (pintype "passive"))
      (node (ref "RL15") (pin "1") (pinfunction "1_1") (pintype "passive"))
    )
    (net (code "142") (name "Net-(HD17-Pad1)") (class "Default")
      (node (ref "HD17") (pin "1") (pinfunction "1_1") (pintype "passive"))
      (node (ref "RL16") (pin "2") (pinfunction "2_2") (pintype "passive"))
    )
    (net (code "143") (name "Net-(HD17-Pad2)") (class "Default")
      (node (ref "HD17") (pin "2") (pinfunction "2_2") (pintype "passive"))
      (node (ref "RL16") (pin "5") (pinfunction "5_5") (pintype "passive"))
    )
    (net (code "144") (name "Net-(HD17-Pad3)") (class "Default")
      (node (ref "HD17") (pin "3") (pinfunction "3_3") (pintype "passive"))
      (node (ref "RL16") (pin "1") (pinfunction "1_1") (pintype "passive"))
    )
    (net (code "145") (name "Net-(U2-CANH)") (class "Default")
      (node (ref "HD1") (pin "2") (pinfunction "2_2") (pintype "passive"))
      (node (ref "R2") (pin "1") (pinfunction "1_1") (pintype "passive"))
      (node (ref "U2") (pin "7") (pinfunction "CANH_7") (pintype "passive"))
    )
    (net (code "146") (name "Net-(U2-CANL)") (class "Default")
      (node (ref "HD1") (pin "1") (pinfunction "1_1") (pintype "passive"))
      (node (ref "R2") (pin "2") (pinfunction "2_2") (pintype "passive"))
      (node (ref "U2") (pin "6") (pinfunction "CANL_6") (pintype "passive"))
    )
    (net (code "147") (name "Net-(U5-A)") (class "Default")
      (node (ref "R8") (pin "2") (pinfunction "2_2") (pintype "passive"))
      (node (ref "U5") (pin "1") (pinfunction "A_1") (pintype "passive"))
    )
    (net (code "148") (name "Net-(U6-A)") (class "Default")
      (node (ref "R9") (pin "2") (pinfunction "2_2") (pintype "passive"))
      (node (ref "U6") (pin "1") (pinfunction "A_1") (pintype "passive"))
    )
    (net (code "149") (name "Net-(U7-A)") (class "Default")
      (node (ref "R10") (pin "2") (pinfunction "2_2") (pintype "passive"))
      (node (ref "U7") (pin "1") (pinfunction "A_1") (pintype "passive"))
    )
    (net (code "150") (name "Net-(U8-A)") (class "Default")
      (node (ref "R11") (pin "2") (pinfunction "2_2") (pintype "passive"))
      (node (ref "U8") (pin "1") (pinfunction "A_1") (pintype "passive"))
    )
    (net (code "151") (name "Net-(U9-A)") (class "Default")
      (node (ref "R12") (pin "2") (pinfunction "2_2") (pintype "passive"))
      (node (ref "U9") (pin "1") (pinfunction "A_1") (pintype "passive"))
    )
    (net (code "152") (name "Net-(U10-A)") (class "Default")
      (node (ref "R13") (pin "2") (pinfunction "2_2") (pintype "passive"))
      (node (ref "U10") (pin "1") (pinfunction "A_1") (pintype "passive"))
    )
    (net (code "153") (name "Net-(U11-A)") (class "Default")
      (node (ref "R14") (pin "2") (pinfunction "2_2") (pintype "passive"))
      (node (ref "U11") (pin "1") (pinfunction "A_1") (pintype "passive"))
    )
    (net (code "154") (name "Net-(U12-A)") (class "Default")
      (node (ref "R15") (pin "2") (pinfunction "2_2") (pintype "passive"))
      (node (ref "U12") (pin "1") (pinfunction "A_1") (pintype "passive"))
    )
    (net (code "155") (name "Net-(U13-A)") (class "Default")
      (node (ref "R24") (pin "2") (pinfunction "2_2") (pintype "passive"))
      (node (ref "U13") (pin "1") (pinfunction "A_1") (pintype "passive"))
    )
    (net (code "156") (name "Net-(U14-A)") (class "Default")
      (node (ref "R25") (pin "2") (pinfunction "2_2") (pintype "passive"))
      (node (ref "U14") (pin "1") (pinfunction "A_1") (pintype "passive"))
    )
    (net (code "157") (name "Net-(U15-A)") (class "Default")
      (node (ref "R26") (pin "2") (pinfunction "2_2") (pintype "passive"))
      (node (ref "U15") (pin "1") (pinfunction "A_1") (pintype "passive"))
    )
    (net (code "158") (name "Net-(U16-A)") (class "Default")
      (node (ref "R27") (pin "2") (pinfunction "2_2") (pintype "passive"))
      (node (ref "U16") (pin "1") (pinfunction "A_1") (pintype "passive"))
    )
    (net (code "159") (name "Net-(U17-A)") (class "Default")
      (node (ref "R28") (pin "2") (pinfunction "2_2") (pintype "passive"))
      (node (ref "U17") (pin "1") (pinfunction "A_1") (pintype "passive"))
    )
    (net (code "160") (name "Net-(U18-A)") (class "Default")
      (node (ref "R29") (pin "2") (pinfunction "2_2") (pintype "passive"))
      (node (ref "U18") (pin "1") (pinfunction "A_1") (pintype "passive"))
    )
    (net (code "161") (name "Net-(U19-A)") (class "Default")
      (node (ref "R30") (pin "2") (pinfunction "2_2") (pintype "passive"))
      (node (ref "U19") (pin "1") (pinfunction "A_1") (pintype "passive"))
    )
    (net (code "162") (name "Net-(U20-A)") (class "Default")
      (node (ref "R31") (pin "2") (pinfunction "2_2") (pintype "passive"))
      (node (ref "U20") (pin "1") (pinfunction "A_1") (pintype "passive"))
    )
    (net (code "163") (name "Net-(U21-A)") (class "Default")
      (node (ref "R72") (pin "2") (pinfunction "2_2") (pintype "passive"))
      (node (ref "U21") (pin "1") (pinfunction "A_1") (pintype "passive"))
    )
    (net (code "164") (name "Net-(U22-A)") (class "Default")
      (node (ref "R73") (pin "2") (pinfunction "2_2") (pintype "passive"))
      (node (ref "U22") (pin "1") (pinfunction "A_1") (pintype "passive"))
    )
    (net (code "165") (name "Net-(U23-A)") (class "Default")
      (node (ref "R74") (pin "2") (pinfunction "2_2") (pintype "passive"))
      (node (ref "U23") (pin "1") (pinfunction "A_1") (pintype "passive"))
    )
    (net (code "166") (name "Net-(U24-A)") (class "Default")
      (node (ref "R75") (pin "2") (pinfunction "2_2") (pintype "passive"))
      (node (ref "U24") (pin "1") (pinfunction "A_1") (pintype "passive"))
    )
    (net (code "167") (name "VCC") (class "Default")
      (node (ref "*2") (pin "2") (pinfunction "V-IN_2") (pintype "passive"))
      (node (ref "C8") (pin "1") (pinfunction "1_1") (pintype "passive"))
      (node (ref "D14") (pin "2") (pinfunction "K_2") (pintype "passive"))
      (node (ref "D15") (pin "2") (pinfunction "K_2") (pintype "passive"))
      (node (ref "D16") (pin "2") (pinfunction "K_2") (pintype "passive"))
      (node (ref "D17") (pin "2") (pinfunction "K_2") (pintype "passive"))
      (node (ref "D18") (pin "2") (pinfunction "K_2") (pintype "passive"))
      (node (ref "D19") (pin "2") (pinfunction "K_2") (pintype "passive"))
      (node (ref "D2") (pin "2") (pinfunction "K_2") (pintype "passive"))
      (node (ref "D26") (pin "2") (pinfunction "K_2") (pintype "passive"))
      (node (ref "D27") (pin "2") (pinfunction "K_2") (pintype "passive"))
      (node (ref "D28") (pin "2") (pinfunction "K_2") (pintype "passive"))
      (node (ref "D29") (pin "2") (pinfunction "K_2") (pintype "passive"))
      (node (ref "D3") (pin "2") (pinfunction "K_2") (pintype "passive"))
      (node (ref "D4") (pin "2") (pinfunction "K_2") (pintype "passive"))
      (node (ref "D5") (pin "2") (pinfunction "K_2") (pintype "passive"))
      (node (ref "D6") (pin "2") (pinfunction "K_2") (pintype "passive"))
      (node (ref "D7") (pin "2") (pinfunction "K_2") (pintype "passive"))
      (node (ref "HD18") (pin "2") (pinfunction "2_2") (pintype "passive"))
      (node (ref "IC1") (pin "10") (pinfunction "COM_10") (pintype "passive"))
      (node (ref "IC2") (pin "10") (pinfunction "COM_10") (pintype "passive"))
      (node (ref "JP4") (pin "1") (pinfunction "1_1") (pintype "passive"))
      (node (ref "R16") (pin "2") (pinfunction "2_2") (pintype "passive"))
      (node (ref "R17") (pin "2") (pinfunction "2_2") (pintype "passive"))
      (node (ref "R18") (pin "2") (pinfunction "2_2") (pintype "passive"))
      (node (ref "R19") (pin "2") (pinfunction "2_2") (pintype "passive"))
      (node (ref "R20") (pin "2") (pinfunction "2_2") (pintype "passive"))
      (node (ref "R21") (pin "2") (pinfunction "2_2") (pintype "passive"))
      (node (ref "R22") (pin "2") (pinfunction "2_2") (pintype "passive"))
      (node (ref "R23") (pin "2") (pinfunction "2_2") (pintype "passive"))
      (node (ref "R32") (pin "2") (pinfunction "2_2") (pintype "passive"))
      (node (ref "R33") (pin "2") (pinfunction "2_2") (pintype "passive"))
      (node (ref "R34") (pin "2") (pinfunction "2_2") (pintype "passive"))
      (node (ref "R35") (pin "2") (pinfunction "2_2") (pintype "passive"))
      (node (ref "R36") (pin "2") (pinfunction "2_2") (pintype "passive"))
      (node (ref "R37") (pin "2") (pinfunction "2_2") (pintype "passive"))
      (node (ref "R38") (pin "2") (pinfunction "2_2") (pintype "passive"))
      (node (ref "R39") (pin "2") (pinfunction "2_2") (pintype "passive"))
      (node (ref "R40") (pin "2") (pinfunction "2_2") (pintype "passive"))
      (node (ref "R41") (pin "2") (pinfunction "2_2") (pintype "passive"))
      (node (ref "R42") (pin "2") (pinfunction "2_2") (pintype "passive"))
      (node (ref "R43") (pin "2") (pinfunction "2_2") (pintype "passive"))
      (node (ref "R44") (pin "2") (pinfunction "2_2") (pintype "passive"))
      (node (ref "R45") (pin "2") (pinfunction "2_2") (pintype "passive"))
      (node (ref "R46") (pin "2") (pinfunction "2_2") (pintype "passive"))
      (node (ref "R47") (pin "2") (pinfunction "2_2") (pintype "passive"))
      (node (ref "R48") (pin "2") (pinfunction "2_2") (pintype "passive"))
      (node (ref "R49") (pin "2") (pinfunction "2_2") (pintype "passive"))
      (node (ref "R50") (pin "2") (pinfunction "2_2") (pintype "passive"))
      (node (ref "R51") (pin "2") (pinfunction "2_2") (pintype "passive"))
      (node (ref "R52") (pin "2") (pinfunction "2_2") (pintype "passive"))
      (node (ref "R53") (pin "2") (pinfunction "2_2") (pintype "passive"))
      (node (ref "R54") (pin "2") (pinfunction "2_2") (pintype "passive"))
      (node (ref "R55") (pin "2") (pinfunction "2_2") (pintype "passive"))
      (node (ref "R56") (pin "2") (pinfunction "2_2") (pintype "passive"))
      (node (ref "R57") (pin "2") (pinfunction "2_2") (pintype "passive"))
      (node (ref "R58") (pin "2") (pinfunction "2_2") (pintype "passive"))
      (node (ref "R59") (pin "2") (pinfunction "2_2") (pintype "passive"))
      (node (ref "R60") (pin "2") (pinfunction "2_2") (pintype "passive"))
      (node (ref "R61") (pin "2") (pinfunction "2_2") (pintype "passive"))
      (node (ref "R62") (pin "2") (pinfunction "2_2") (pintype "passive"))
      (node (ref "R63") (pin "2") (pinfunction "2_2") (pintype "passive"))
      (node (ref "R64") (pin "2") (pinfunction "2_2") (pintype "passive"))
      (node (ref "R65") (pin "2") (pinfunction "2_2") (pintype "passive"))
      (node (ref "R66") (pin "2") (pinfunction "2_2") (pintype "passive"))
      (node (ref "R67") (pin "2") (pinfunction "2_2") (pintype "passive"))
      (node (ref "R68") (pin "2") (pinfunction "2_2") (pintype "passive"))
      (node (ref "R69") (pin "2") (pinfunction "2_2") (pintype "passive"))
      (node (ref "R70") (pin "2") (pinfunction "2_2") (pintype "passive"))
      (node (ref "R71") (pin "2") (pinfunction "2_2") (pintype "passive"))
      (node (ref "R72") (pin "1") (pinfunction "1_1") (pintype "passive"))
      (node (ref "R73") (pin "1") (pinfunction "1_1") (pintype "passive"))
      (node (ref "R74") (pin "1") (pinfunction "1_1") (pintype "passive"))
      (node (ref "R75") (pin "1") (pinfunction "1_1") (pintype "passive"))
      (node (ref "RL1") (pin "3") (pinfunction "3_3") (pintype "passive"))
      (node (ref "RL10") (pin "3") (pinfunction "3_3") (pintype "passive"))
      (node (ref "RL11") (pin "3") (pinfunction "3_3") (pintype "passive"))
      (node (ref "RL12") (pin "3") (pinfunction "3_3") (pintype "passive"))
      (node (ref "RL13") (pin "3") (pinfunction "3_3") (pintype "passive"))
      (node (ref "RL14") (pin "3") (pinfunction "3_3") (pintype "passive"))
      (node (ref "RL15") (pin "3") (pinfunction "3_3") (pintype "passive"))
      (node (ref "RL16") (pin "3") (pinfunction "3_3") (pintype "passive"))
      (node (ref "RL2") (pin "3") (pinfunction "3_3") (pintype "passive"))
      (node (ref "RL3") (pin "3") (pinfunction "3_3") (pintype "passive"))
      (node (ref "RL4") (pin "3") (pinfunction "3_3") (pintype "passive"))
      (node (ref "RL5") (pin "3") (pinfunction "3_3") (pintype "passive"))
      (node (ref "RL6") (pin "3") (pinfunction "3_3") (pintype "passive"))
      (node (ref "RL7") (pin "3") (pinfunction "3_3") (pintype "passive"))
      (node (ref "RL8") (pin "3") (pinfunction "3_3") (pintype "passive"))
      (node (ref "RL9") (pin "3") (pinfunction "3_3") (pintype "passive"))
    )
    (net (code "168") (name "VCC_ISO") (class "Default")
      (node (ref "*2") (pin "4") (pinfunction "Vout_4") (pintype "passive"))
      (node (ref "C4") (pin "1") (pinfunction "1_1") (pintype "passive"))
      (node (ref "C6") (pin "1") (pinfunction "1_1") (pintype "passive"))
      (node (ref "R10") (pin "1") (pinfunction "1_1") (pintype "passive"))
      (node (ref "R11") (pin "1") (pinfunction "1_1") (pintype "passive"))
      (node (ref "R12") (pin "1") (pinfunction "1_1") (pintype "passive"))
      (node (ref "R13") (pin "1") (pinfunction "1_1") (pintype "passive"))
      (node (ref "R14") (pin "1") (pinfunction "1_1") (pintype "passive"))
      (node (ref "R15") (pin "1") (pinfunction "1_1") (pintype "passive"))
      (node (ref "R24") (pin "1") (pinfunction "1_1") (pintype "passive"))
      (node (ref "R25") (pin "1") (pinfunction "1_1") (pintype "passive"))
      (node (ref "R26") (pin "1") (pinfunction "1_1") (pintype "passive"))
      (node (ref "R27") (pin "1") (pinfunction "1_1") (pintype "passive"))
      (node (ref "R28") (pin "1") (pinfunction "1_1") (pintype "passive"))
      (node (ref "R29") (pin "1") (pinfunction "1_1") (pintype "passive"))
      (node (ref "R30") (pin "1") (pinfunction "1_1") (pintype "passive"))
      (node (ref "R31") (pin "1") (pinfunction "1_1") (pintype "passive"))
      (node (ref "R8") (pin "1") (pinfunction "1_1") (pintype "passive"))
      (node (ref "R9") (pin "1") (pinfunction "1_1") (pintype "passive"))
      (node (ref "U1") (pin "3") (pinfunction "Vin_3") (pintype "passive"))
    )
    (net (code "169") (name "unconnected-(U2-Vref-Pad5)") (class "Default")
      (node (ref "U2") (pin "5") (pinfunction "Vref_5") (pintype "passive+no_connect"))
    )
  )
)
